# ACC-MB-R0.net
KiCad netlist of a schematic drawn in EAGLE
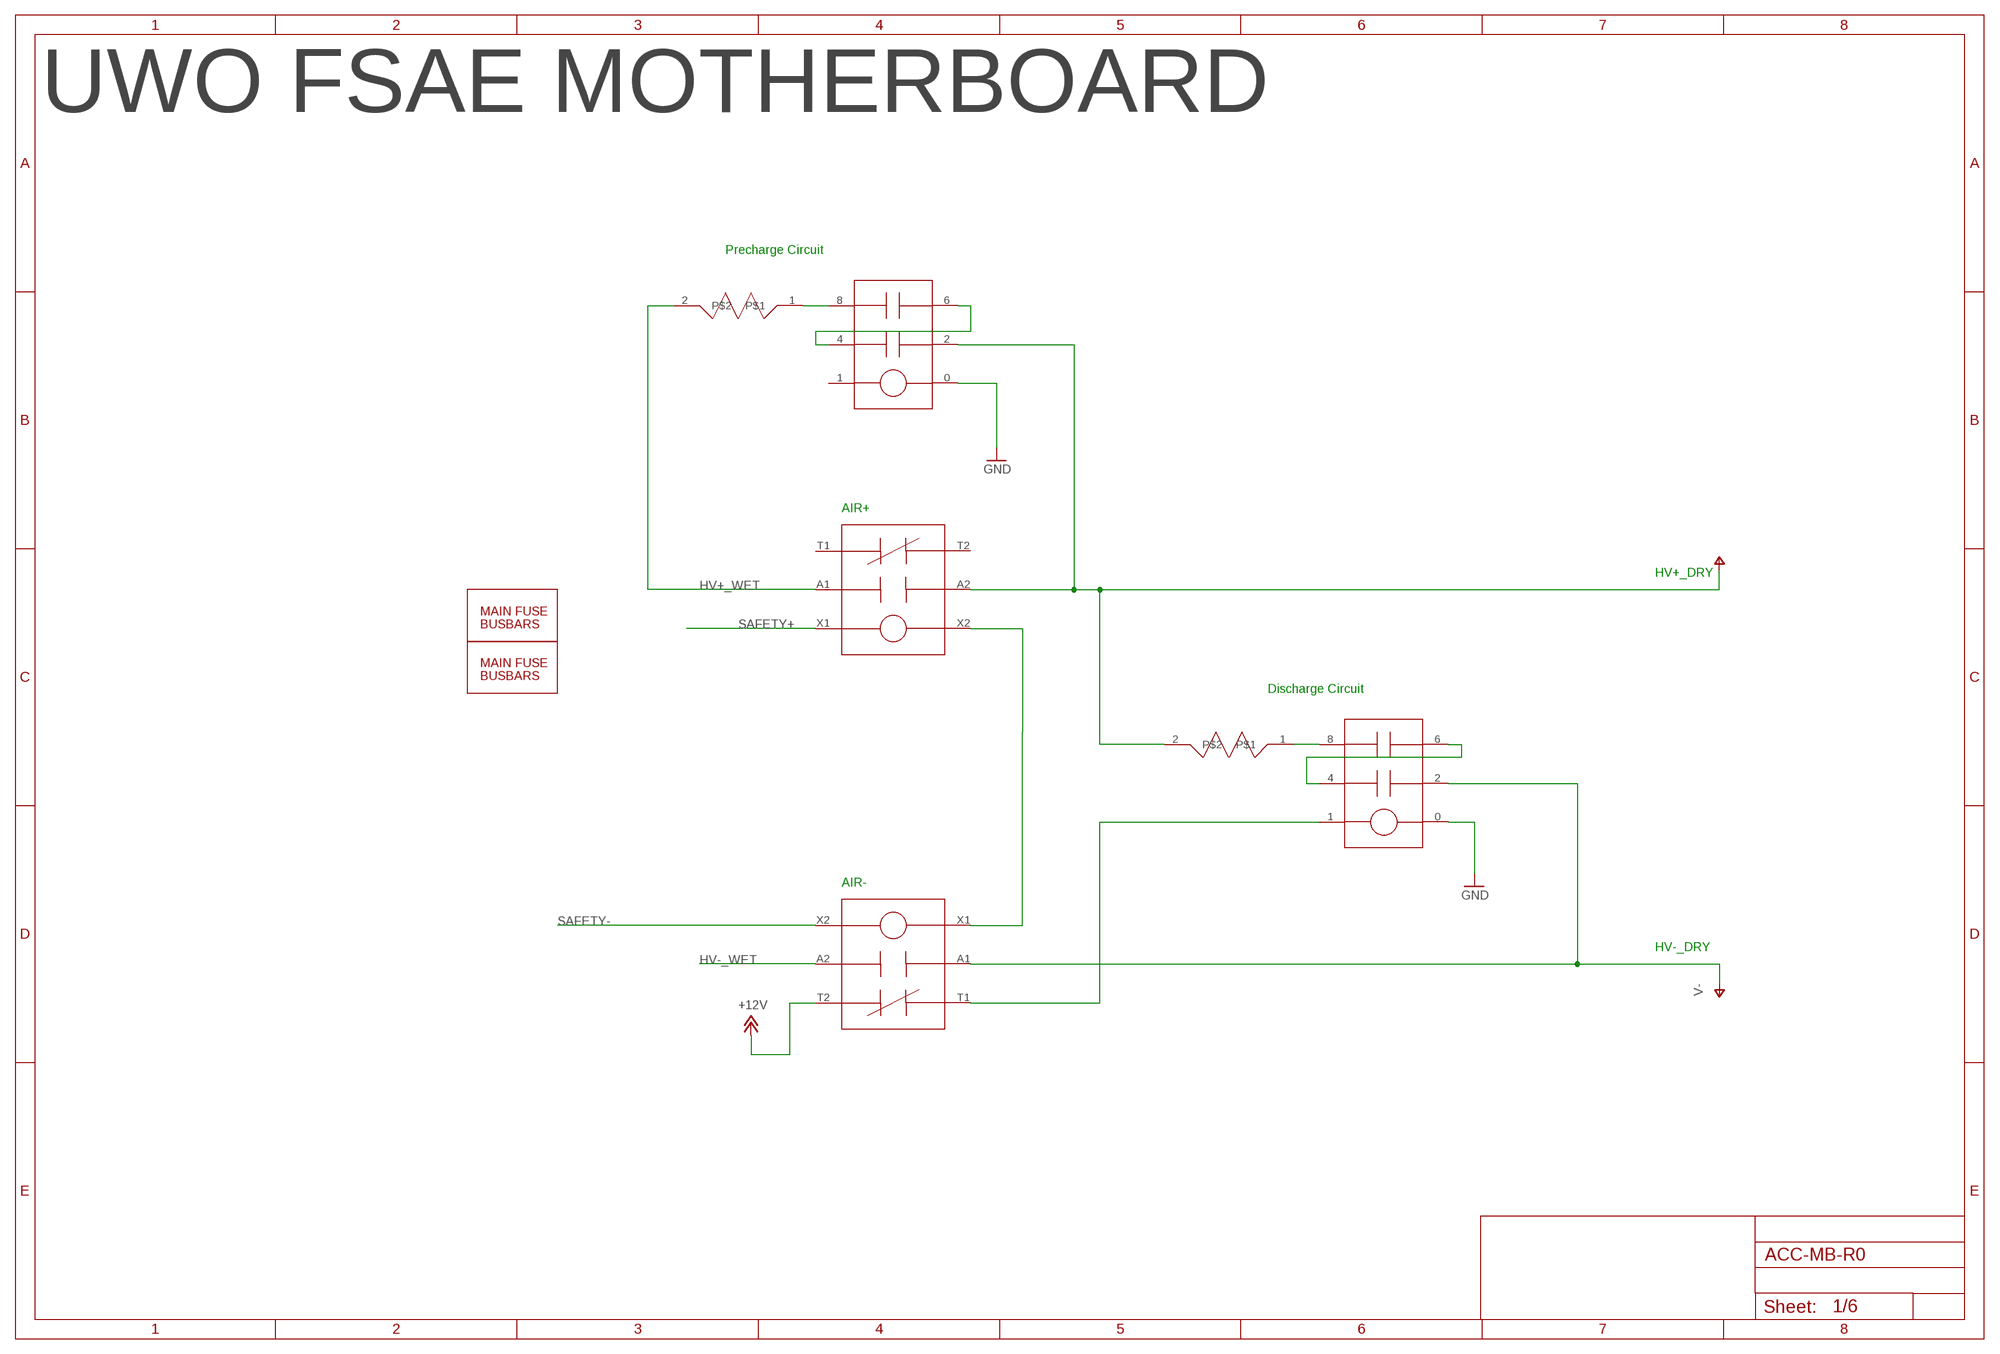
[diagram p0: schematic, sheet 1]
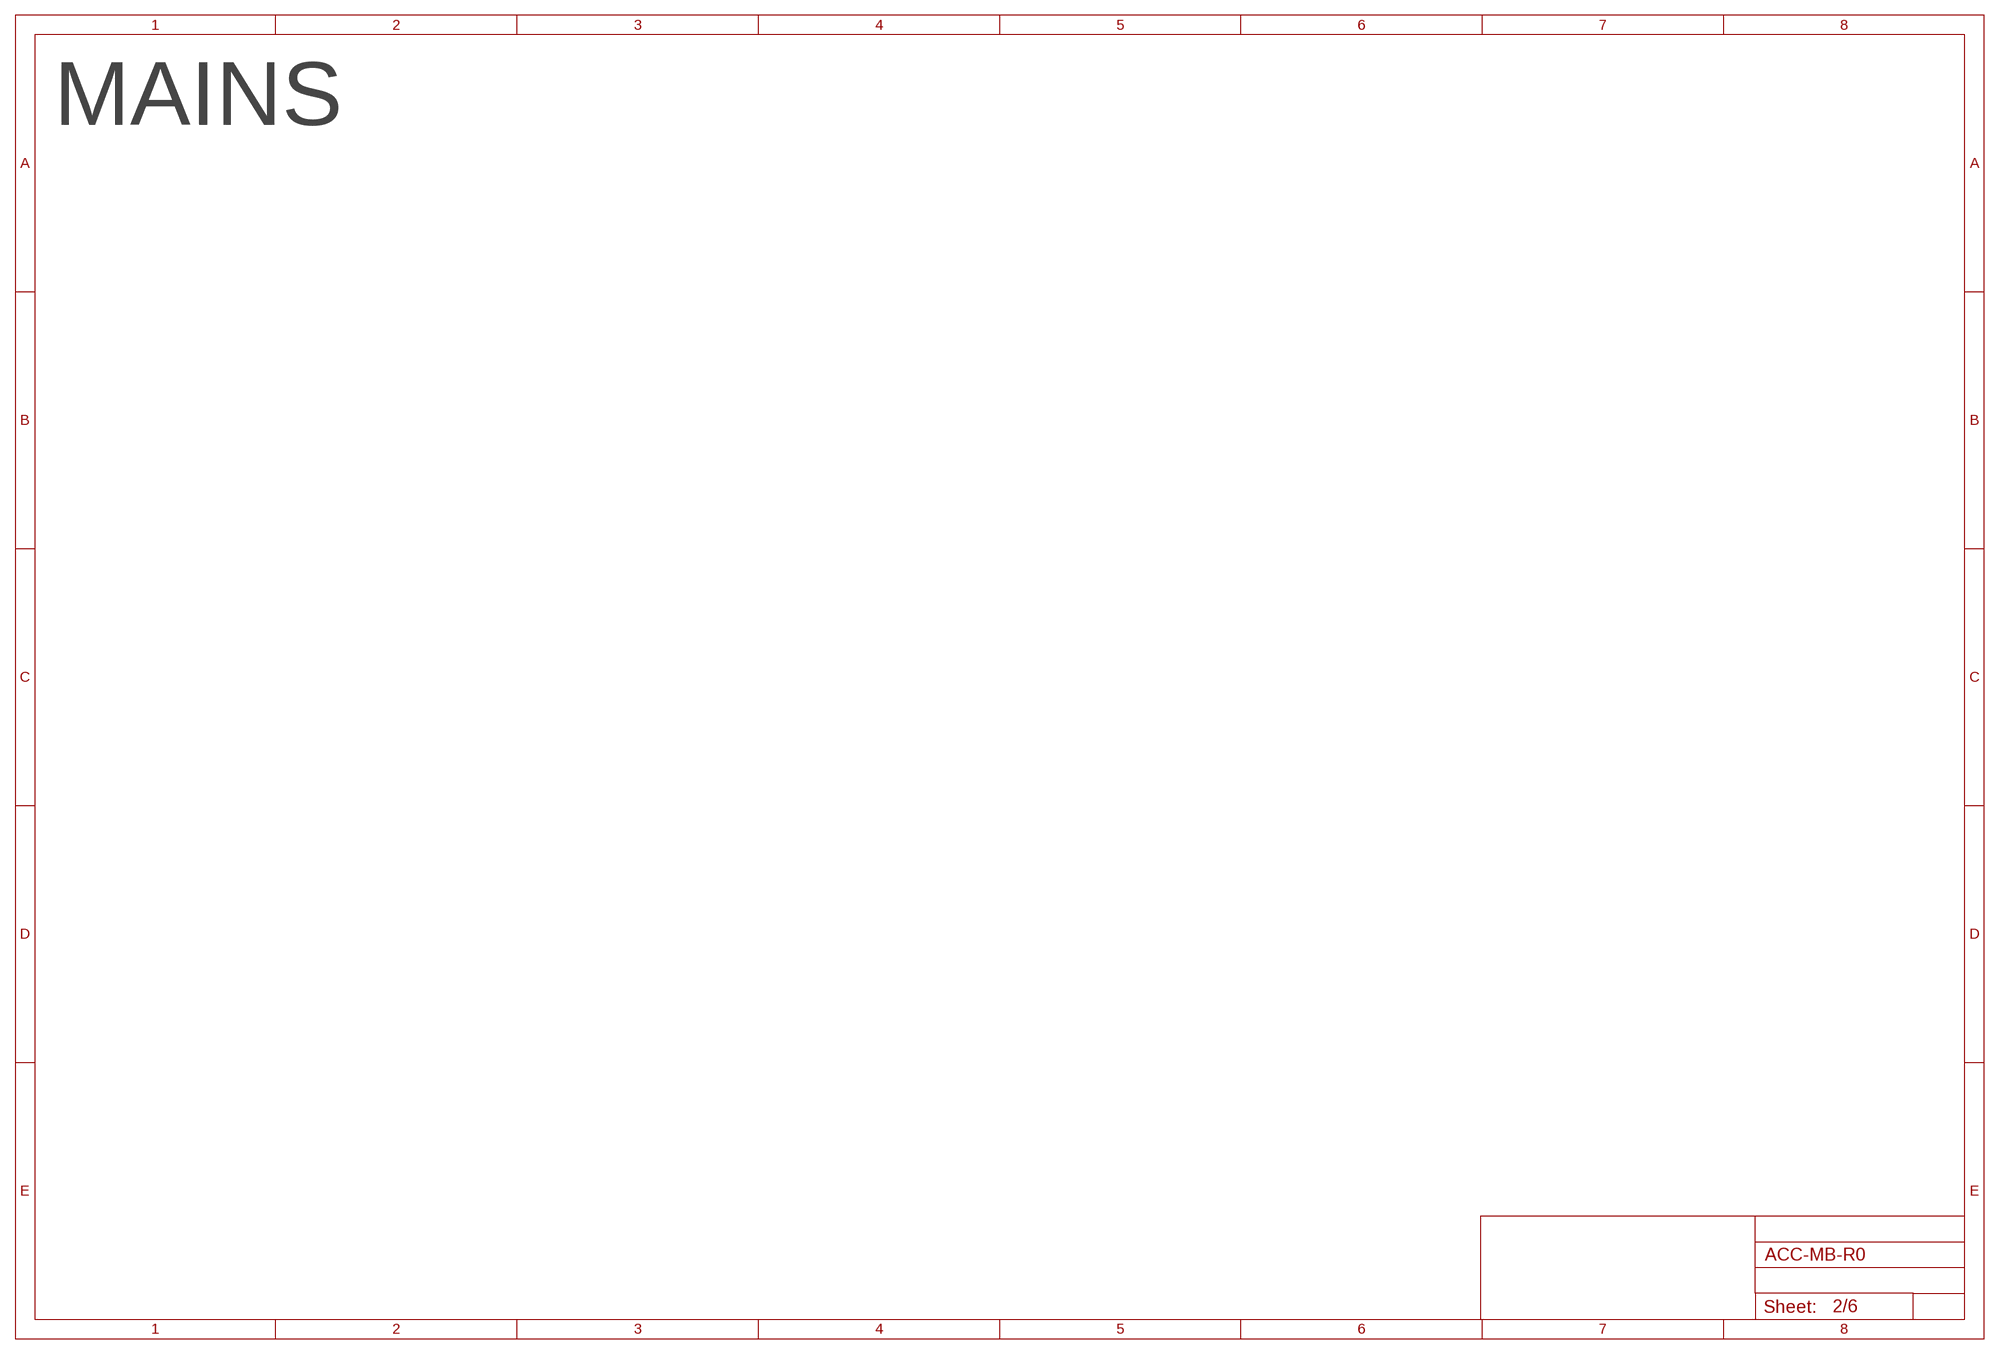
[diagram p1: schematic, sheet 2]
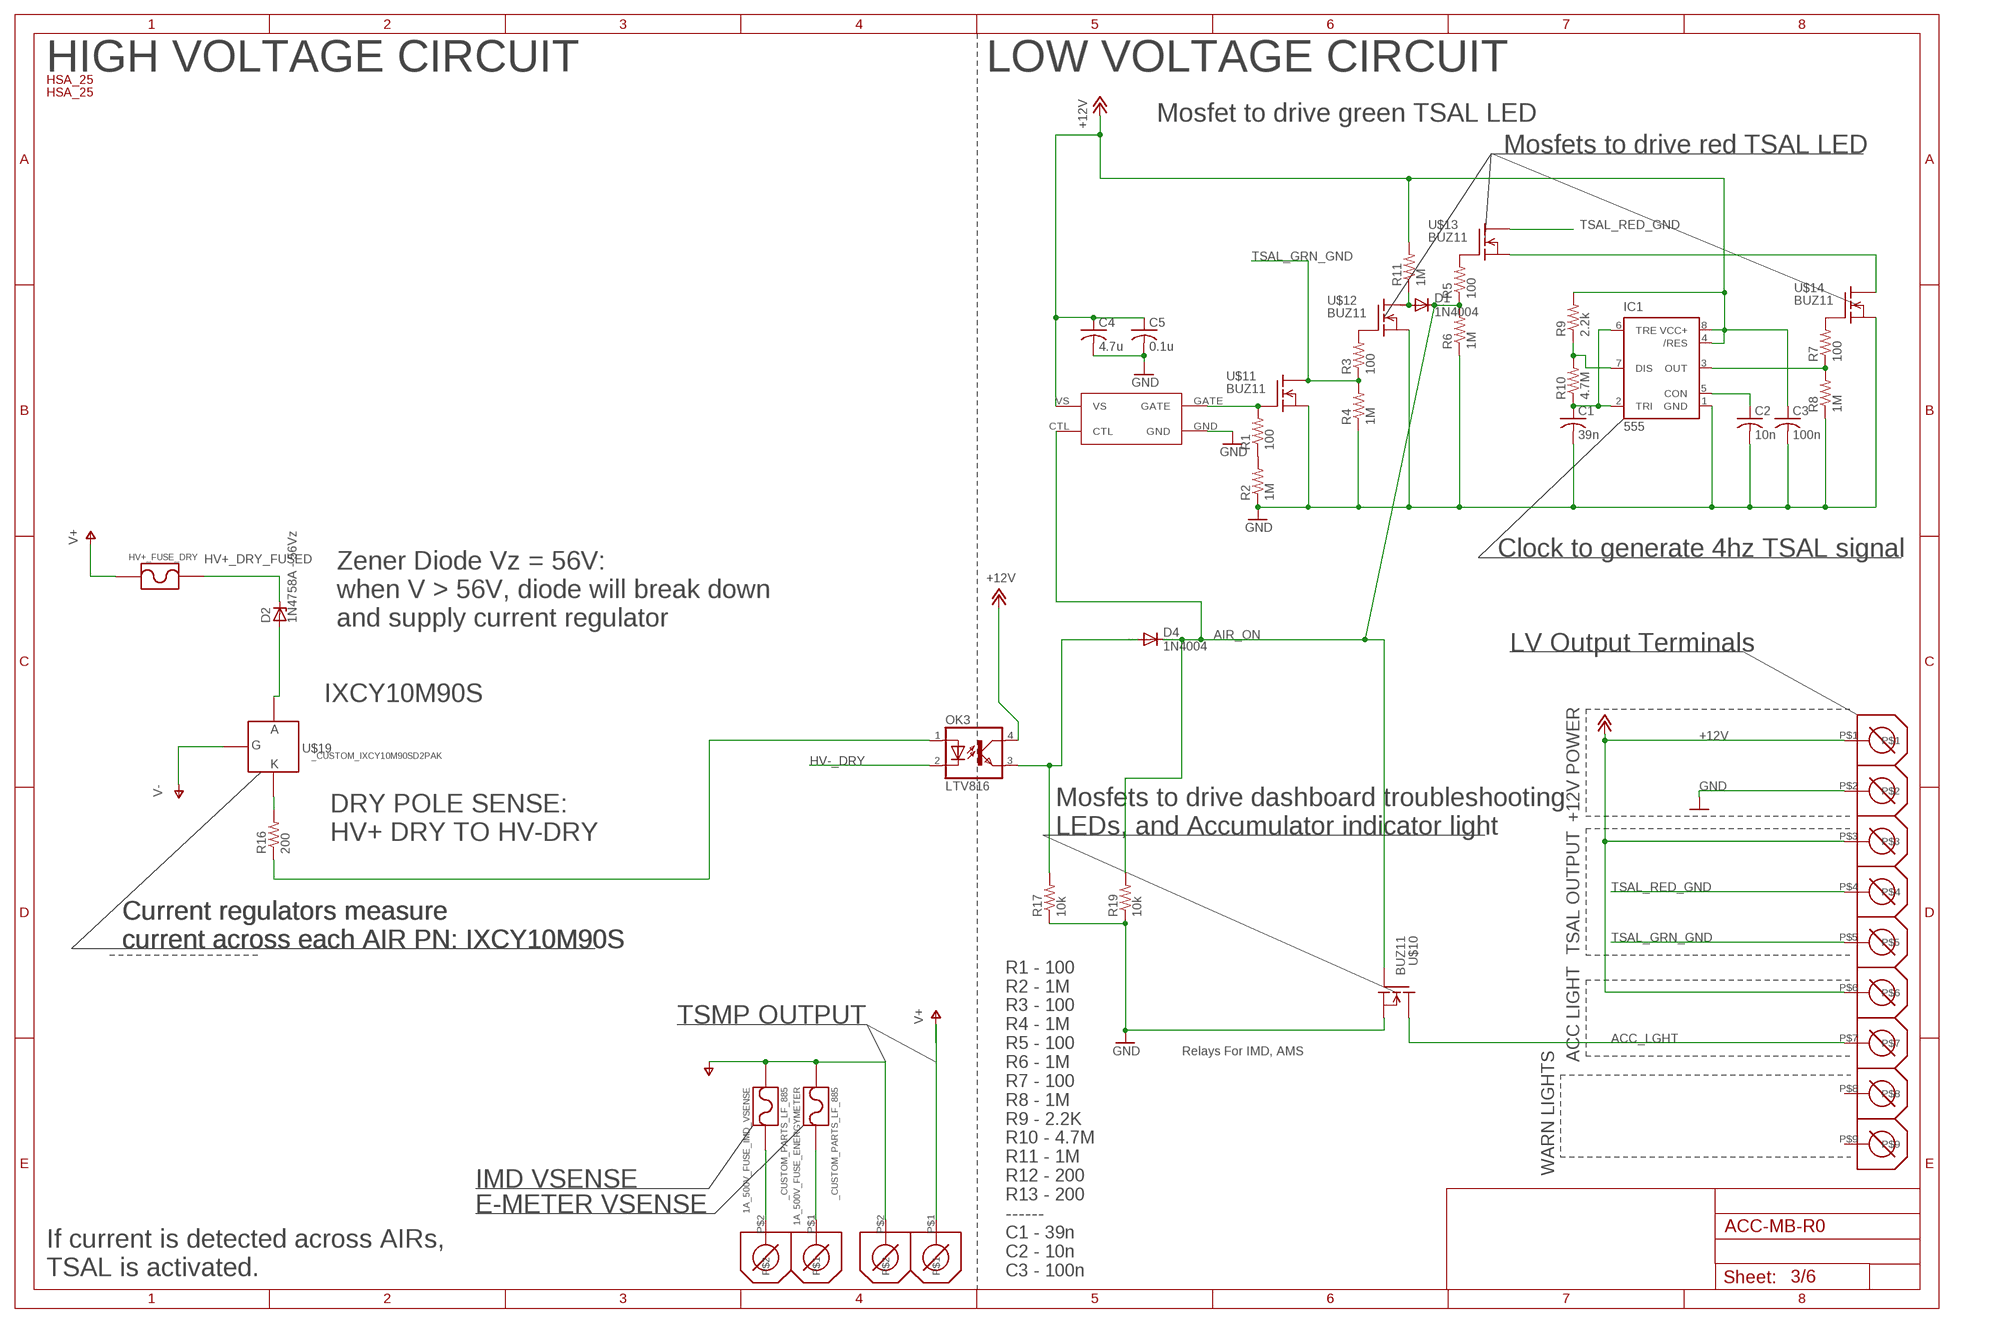
[diagram p2: schematic, sheet 3]
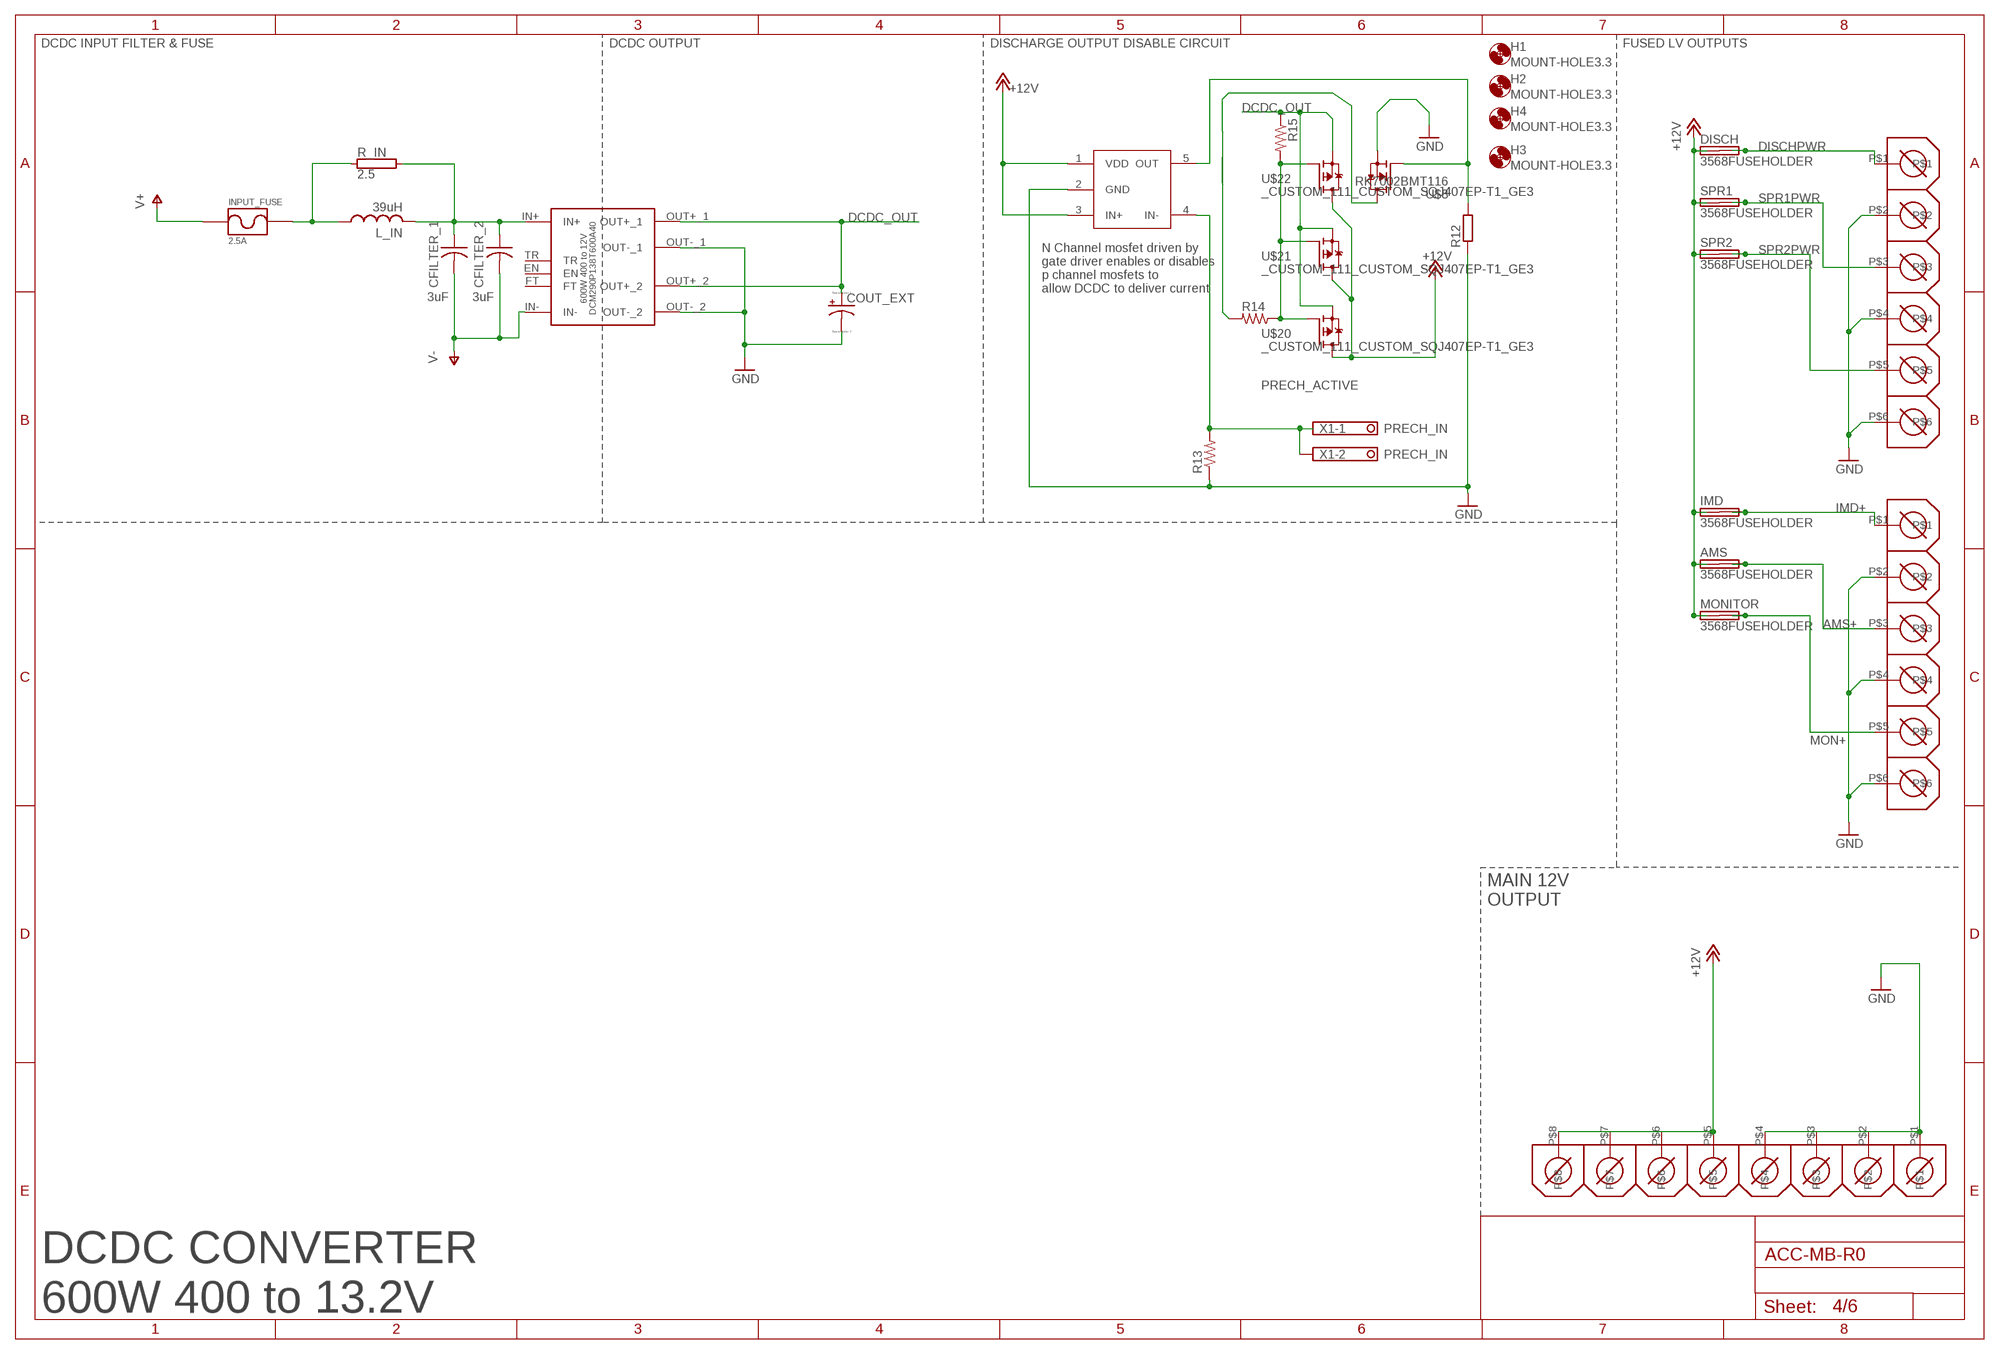
[diagram p3: schematic, sheet 4]
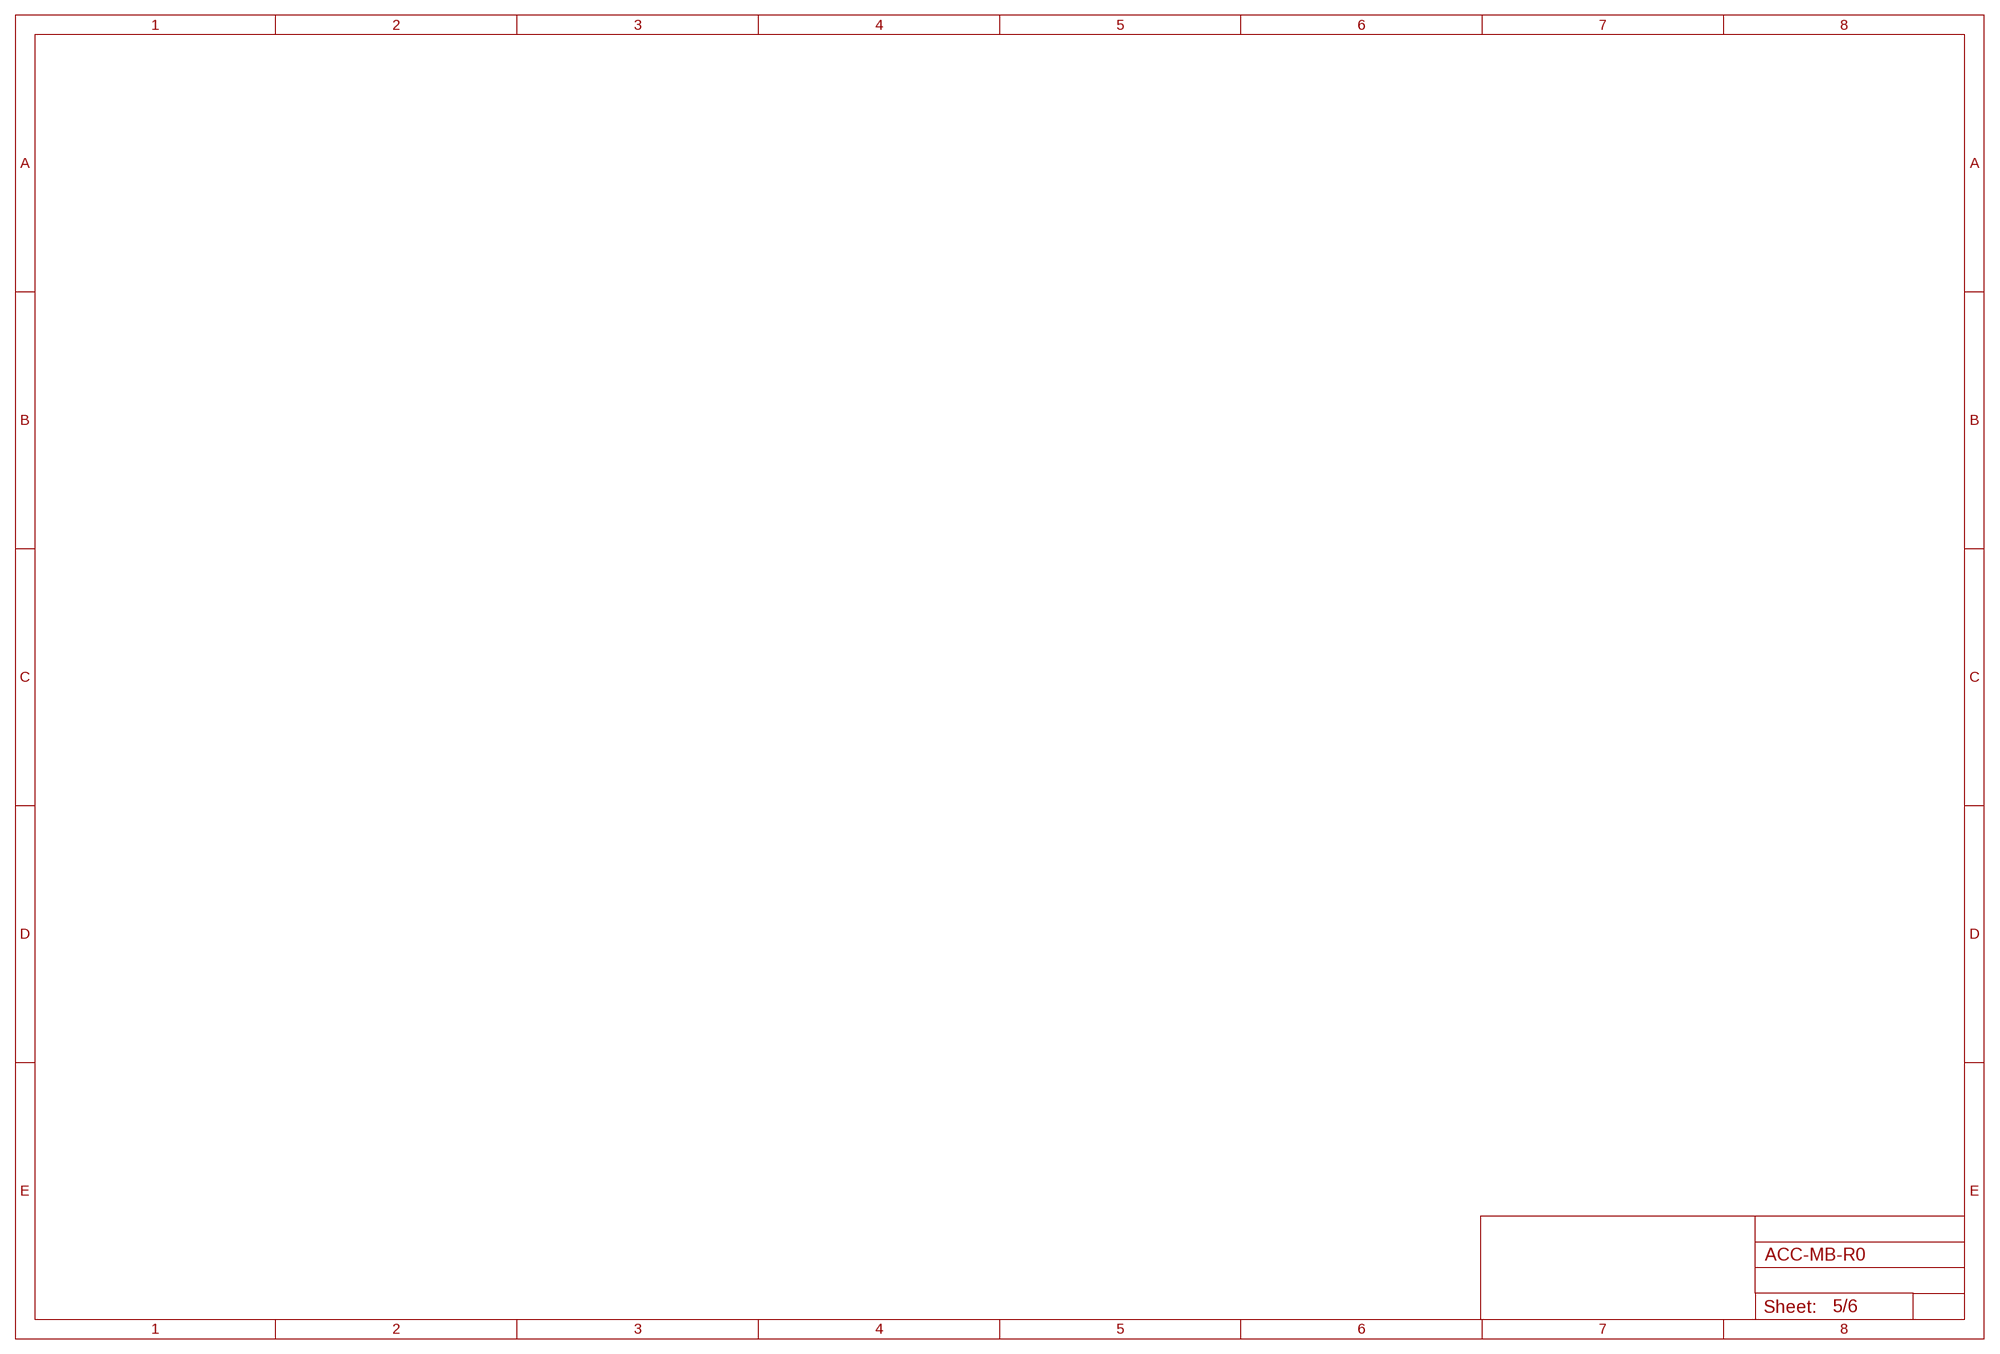
[diagram p4: schematic, sheet 5]
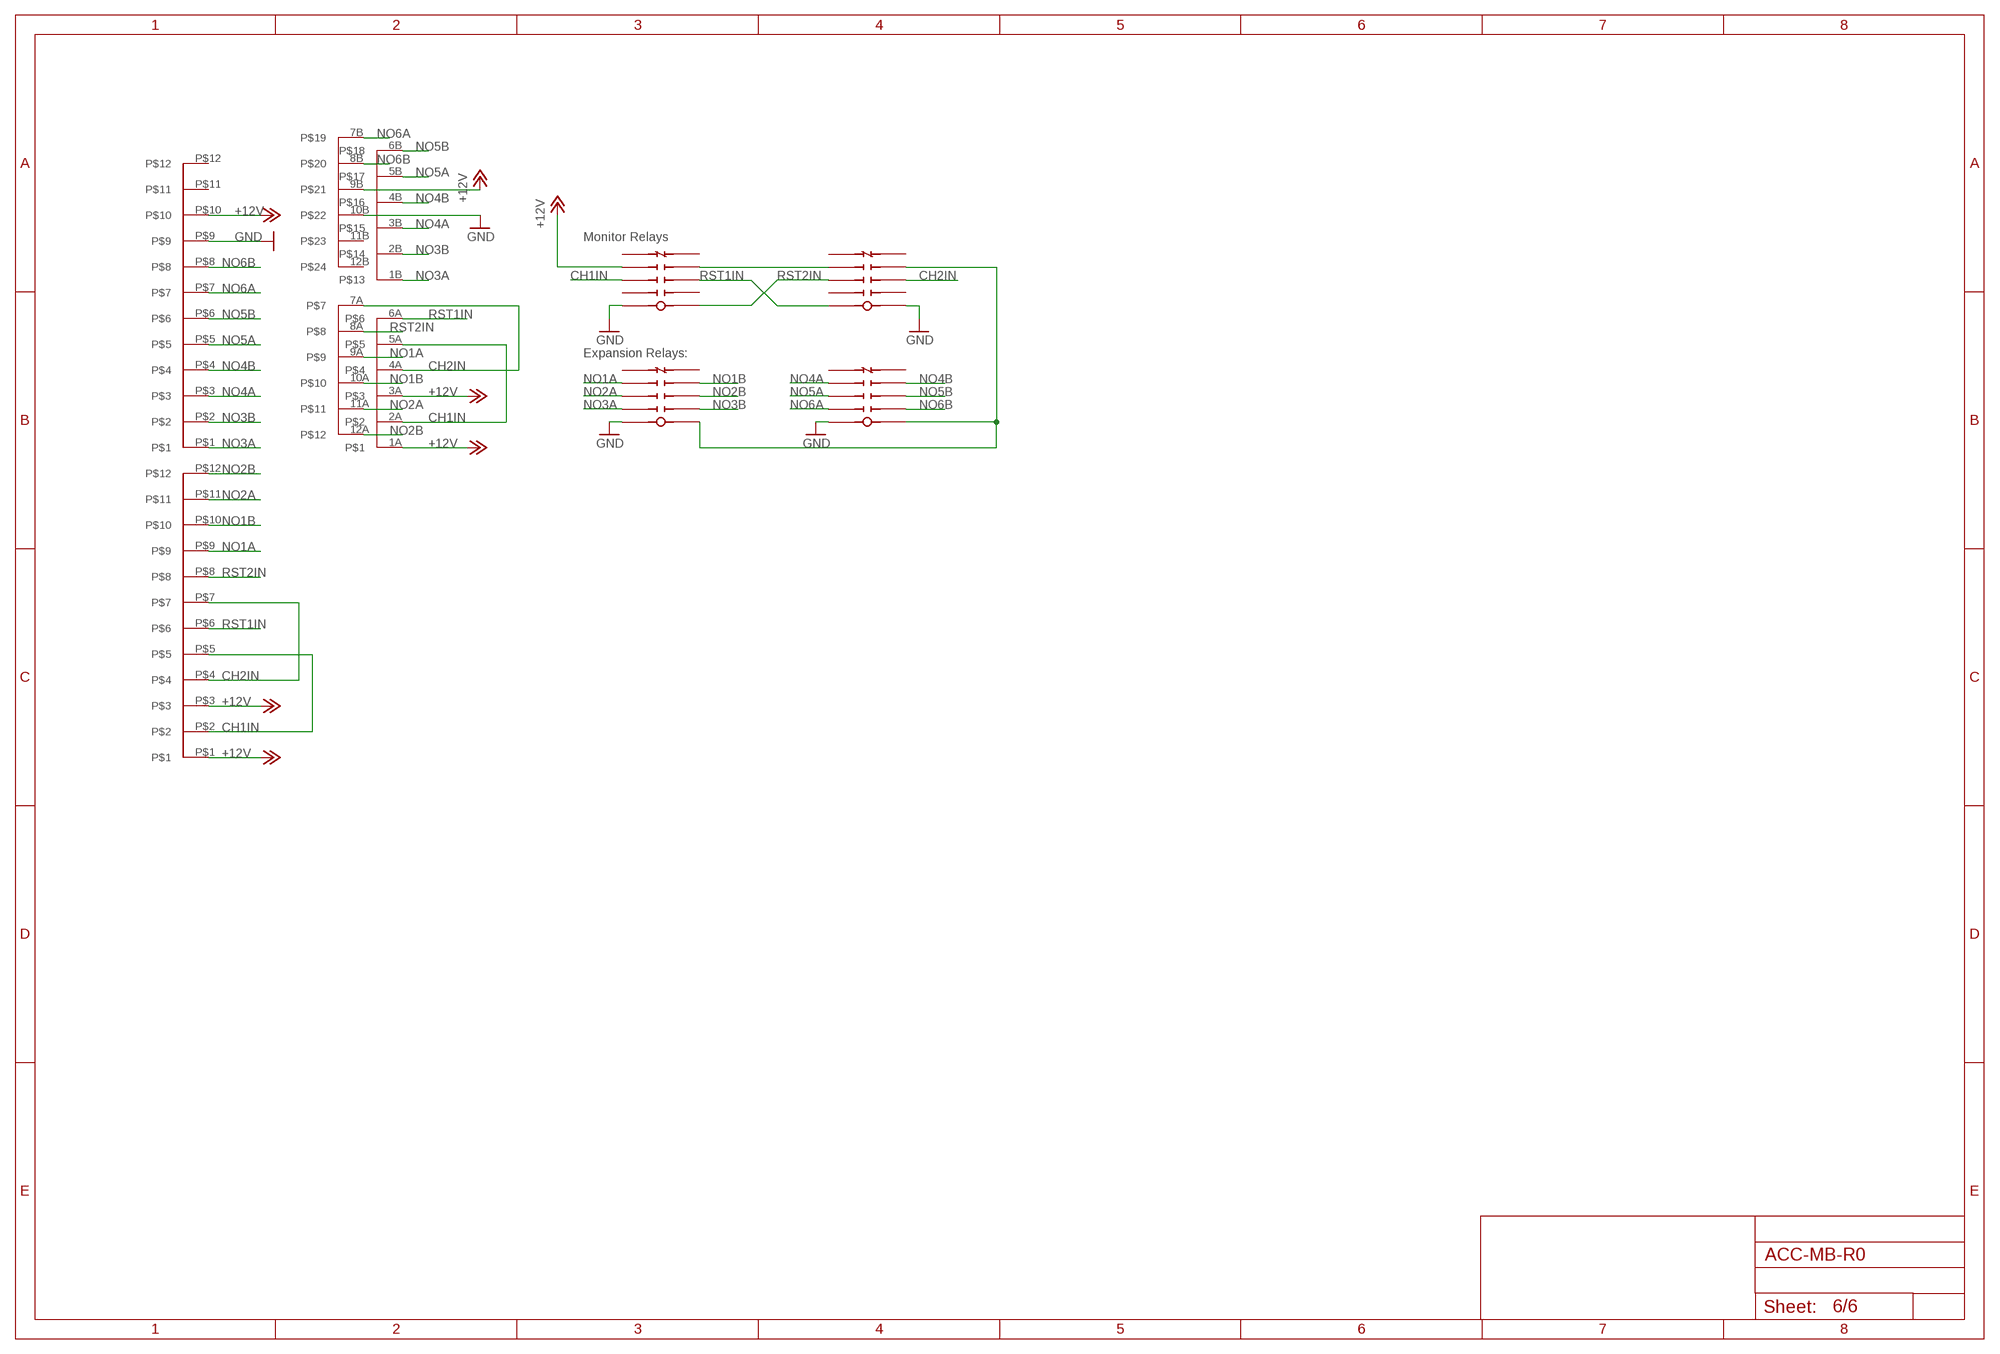
[diagram p5: schematic, sheet 6]

(export (version "E")
  (design (tool "Eeschema 10.0.6"))
  (components
    (comp (ref "1A_500V_FUSE_ENERGYMETER")
      (value "_CUSTOM_PARTS_LF_885")
      (footprint "eagle-import:_CUSTOM_PARTS_LF_885")
      (libsource (lib "eagle-import") (part "_CUSTOM_PARTS_LF_885"))
    )
    (comp (ref "1A_500V_FUSE_IMD_VSENSE")
      (value "_CUSTOM_PARTS_LF_885")
      (footprint "eagle-import:_CUSTOM_PARTS_LF_885")
      (libsource (lib "eagle-import") (part "_CUSTOM_PARTS_LF_885"))
    )
    (comp (ref "C1")
      (value "39n")
      (footprint "eagle-import:C0805")
      (libsource (lib "eagle-import") (part "C-USC0805"))
    )
    (comp (ref "C2")
      (value "10n")
      (footprint "eagle-import:C0805")
      (libsource (lib "eagle-import") (part "C-USC0805"))
    )
    (comp (ref "C3")
      (value "100n")
      (footprint "eagle-import:C0805")
      (libsource (lib "eagle-import") (part "C-USC0805"))
    )
    (comp (ref "C4")
      (value "4.7u")
      (footprint "eagle-import:C0805")
      (libsource (lib "eagle-import") (part "C-USC0805"))
    )
    (comp (ref "C5")
      (value "0.1u")
      (footprint "eagle-import:C0805")
      (libsource (lib "eagle-import") (part "C-USC0805"))
    )
    (comp (ref "D1")
      (value "1N4004")
      (footprint "eagle-import:DO41-10")
      (libsource (lib "eagle-import") (part "1N4004"))
    )
    (comp (ref "D2")
      (value "1N4758A - 56Vz")
      (footprint "eagle-import:ZDIO12.5")
      (libsource (lib "eagle-import") (part "ZENER-DIODEZD-12.5"))
    )
    (comp (ref "D4")
      (value "1N4004")
      (footprint "eagle-import:DO41-10")
      (libsource (lib "eagle-import") (part "1N4004"))
    )
    (comp (ref "HV+_FUSE_DRY")
      (value "_CUSTOM_PARTS_LF_885")
      (footprint "eagle-import:_CUSTOM_PARTS_LF_885")
      (libsource (lib "eagle-import") (part "_CUSTOM_PARTS_LF_885"))
    )
    (comp (ref "IC1")
      (value "555")
      (footprint "eagle-import:DIP08")
      (libsource (lib "eagle-import") (part "555P"))
    )
    (comp (ref "OK3")
      (value "LTV816")
      (footprint "eagle-import:DIL04")
      (libsource (lib "eagle-import") (part "LTV816"))
    )
    (comp (ref "R1")
      (value "100")
      (footprint "eagle-import:R0805_1")
      (libsource (lib "eagle-import") (part "R-US_?{colon}1R0805"))
    )
    (comp (ref "R2")
      (value "1M")
      (footprint "eagle-import:R0805_1")
      (libsource (lib "eagle-import") (part "R-US_?{colon}1R0805"))
    )
    (comp (ref "R3")
      (value "100")
      (footprint "eagle-import:R0805_1")
      (libsource (lib "eagle-import") (part "R-US_?{colon}1R0805"))
    )
    (comp (ref "R4")
      (value "1M")
      (footprint "eagle-import:R0805_1")
      (libsource (lib "eagle-import") (part "R-US_?{colon}1R0805"))
    )
    (comp (ref "R5")
      (value "100")
      (footprint "eagle-import:R0805_1")
      (libsource (lib "eagle-import") (part "R-US_?{colon}1R0805"))
    )
    (comp (ref "R6")
      (value "1M")
      (footprint "eagle-import:R0805_1")
      (libsource (lib "eagle-import") (part "R-US_?{colon}1R0805"))
    )
    (comp (ref "R7")
      (value "100")
      (footprint "eagle-import:R0805_1")
      (libsource (lib "eagle-import") (part "R-US_?{colon}1R0805"))
    )
    (comp (ref "R8")
      (value "1M")
      (footprint "eagle-import:R0805_1")
      (libsource (lib "eagle-import") (part "R-US_?{colon}1R0805"))
    )
    (comp (ref "R9")
      (value "2.2k")
      (footprint "eagle-import:R0805_1")
      (libsource (lib "eagle-import") (part "R-US_?{colon}1R0805"))
    )
    (comp (ref "R10")
      (value "4.7M")
      (footprint "eagle-import:R0805_1")
      (libsource (lib "eagle-import") (part "R-US_?{colon}1R0805"))
    )
    (comp (ref "R11")
      (value "1M")
      (footprint "eagle-import:R0805_1")
      (libsource (lib "eagle-import") (part "R-US_?{colon}1R0805"))
    )
    (comp (ref "R16")
      (value "200")
      (footprint "eagle-import:R2010")
      (libsource (lib "eagle-import") (part "R-US_R2010"))
    )
    (comp (ref "R17")
      (value "10k")
      (footprint "eagle-import:R0805_1")
      (libsource (lib "eagle-import") (part "R-US_?{colon}1R0805"))
    )
    (comp (ref "R19")
      (value "10k")
      (footprint "eagle-import:R0805_1")
      (libsource (lib "eagle-import") (part "R-US_?{colon}1R0805"))
    )
    (comp (ref "U$2")
      (value "HSA25")
      (footprint "eagle-import:HSA_25_FOOT")
      (libsource (lib "eagle-import") (part "HSA25"))
    )
    (comp (ref "U$3")
      (value "HSA25")
      (footprint "eagle-import:HSA_25_FOOT")
      (libsource (lib "eagle-import") (part "HSA25"))
    )
    (comp (ref "U$7")
      (value "PHOENIX_1725724")
      (footprint "eagle-import:1725724_FOOT")
      (libsource (lib "eagle-import") (part "PHOENIX_1725724"))
    )
    (comp (ref "U$10")
      (value "BUZ11")
      (footprint "eagle-import:TO220")
      (libsource (lib "eagle-import") (part "BUZ11"))
    )
    (comp (ref "U$11")
      (value "BUZ11")
      (footprint "eagle-import:TO220")
      (libsource (lib "eagle-import") (part "BUZ11"))
    )
    (comp (ref "U$12")
      (value "BUZ11")
      (footprint "eagle-import:TO220")
      (libsource (lib "eagle-import") (part "BUZ11"))
    )
    (comp (ref "U$13")
      (value "BUZ11")
      (footprint "eagle-import:TO220")
      (libsource (lib "eagle-import") (part "BUZ11"))
    )
    (comp (ref "U$14")
      (value "BUZ11")
      (footprint "eagle-import:TO220")
      (libsource (lib "eagle-import") (part "BUZ11"))
    )
    (comp (ref "U$15")
      (value "MIC4417")
      (footprint "eagle-import:PDM_2019_REVB_MIC4416YM4-TR")
      (libsource (lib "eagle-import") (part "MIC4417"))
    )
    (comp (ref "U$16")
      (value "DCDC_PARTS_282838-2_TE")
      (footprint "eagle-import:DCDC_PARTS_282838-2_FOOT")
      (libsource (lib "eagle-import") (part "DCDC_PARTS_282838-2_TE"))
    )
    (comp (ref "U$17")
      (value "DCDC_PARTS_282838-2_TE")
      (footprint "eagle-import:DCDC_PARTS_282838-2_FOOT")
      (libsource (lib "eagle-import") (part "DCDC_PARTS_282838-2_TE"))
    )
    (comp (ref "U$19")
      (value "_CUSTOM_IXCY10M90SD2PAK")
      (footprint "eagle-import:TO228P991X238-3")
      (libsource (lib "eagle-import") (part "_CUSTOM_IXCY10M90SD2PAK"))
    )
    (comp (ref "U$1")
      (value "G7L")
      (footprint "eagle-import:G7L")
      (libsource (lib "eagle-import") (part "G7L"))
    )
    (comp (ref "U$4")
      (value "TO247RESISTORHEATINK")
      (footprint "eagle-import:_CUSTOM_TO-247-2V")
      (libsource (lib "eagle-import") (part "TO247RESISTORHEATINK"))
    )
    (comp (ref "U$24")
      (value "FUSE_HOLDER")
      (footprint "eagle-import:FUSE_HOLDER")
      (libsource (lib "eagle-import") (part "FUSE_HOLDER"))
    )
    (comp (ref "U$31")
      (value "GV224")
      (footprint "eagle-import:GV224")
      (libsource (lib "eagle-import") (part "GV224"))
    )
    (comp (ref "U$32")
      (value "GV224")
      (footprint "eagle-import:GV224")
      (libsource (lib "eagle-import") (part "GV224"))
    )
    (comp (ref "U$33")
      (value "FUSE_HOLDER")
      (footprint "eagle-import:FUSE_HOLDER")
      (libsource (lib "eagle-import") (part "FUSE_HOLDER"))
    )
    (comp (ref "U$34")
      (value "G7L")
      (footprint "eagle-import:G7L")
      (libsource (lib "eagle-import") (part "G7L"))
    )
    (comp (ref "U$35")
      (value "TO247RESISTORHEATINK")
      (footprint "eagle-import:_CUSTOM_TO-247-2V")
      (libsource (lib "eagle-import") (part "TO247RESISTORHEATINK"))
    )
    (comp (ref "U$23")
      (value "1777642_PHOENIX")
      (footprint "eagle-import:1777642_FOOTPRINT")
      (libsource (lib "eagle-import") (part "1777642_PHOENIX"))
    )
    (comp (ref "U$25")
      (value "1777642_PHOENIX")
      (footprint "eagle-import:1777642_FOOTPRINT")
      (libsource (lib "eagle-import") (part "1777642_PHOENIX"))
    )
    (comp (ref "U$26")
      (value "DTM1312PA12BR008")
      (footprint "eagle-import:DE_12X2_PIN_HEADER")
      (libsource (lib "eagle-import") (part "DTM1312PA12BR008"))
    )
    (comp (ref "U$27")
      (value "SR4M4012_TE")
      (footprint "eagle-import:SR4M4012_FOOT")
      (libsource (lib "eagle-import") (part "SR4M4012_TE"))
    )
    (comp (ref "U$28")
      (value "SR4M4012_TE")
      (footprint "eagle-import:SR4M4012_FOOT")
      (libsource (lib "eagle-import") (part "SR4M4012_TE"))
    )
    (comp (ref "U$29")
      (value "SR4M4012_TE")
      (footprint "eagle-import:SR4M4012_FOOT")
      (libsource (lib "eagle-import") (part "SR4M4012_TE"))
    )
    (comp (ref "U$30")
      (value "SR4M4012_TE")
      (footprint "eagle-import:SR4M4012_FOOT")
      (libsource (lib "eagle-import") (part "SR4M4012_TE"))
    )
    (comp (ref "AMS")
      (value "3568FUSEHOLDER")
      (footprint "eagle-import:3568")
      (libsource (lib "eagle-import") (part "3568FUSEHOLDER"))
    )
    (comp (ref "CFILTER_1")
      (value "3uF")
      (footprint "eagle-import:CERALINK_FA3")
      (libsource (lib "eagle-import") (part "B58035U5305M062"))
    )
    (comp (ref "CFILTER_2")
      (value "3uF")
      (footprint "eagle-import:CERALINK_FA3")
      (libsource (lib "eagle-import") (part "B58035U5305M062"))
    )
    (comp (ref "COUT_EXT")
      (value "CPOL-USE7.5-16")
      (footprint "eagle-import:E7,5-16")
      (libsource (lib "eagle-import") (part "CPOL-USE7.5-16"))
    )
    (comp (ref "DCM290P138T600A40")
      (value "600W 400 to 12V")
      (footprint "eagle-import:VICOR_CHIP_HEATSINK")
      (libsource (lib "eagle-import") (part "VICOR_CHIP_WITH_HEATSINK"))
    )
    (comp (ref "DISCH")
      (value "3568FUSEHOLDER")
      (footprint "eagle-import:3568")
      (libsource (lib "eagle-import") (part "3568FUSEHOLDER"))
    )
    (comp (ref "H1")
      (value "MOUNT-HOLE3.3")
      (footprint "eagle-import:3,3")
      (libsource (lib "eagle-import") (part "MOUNT-HOLE3.3"))
    )
    (comp (ref "H2")
      (value "MOUNT-HOLE3.3")
      (footprint "eagle-import:3,3")
      (libsource (lib "eagle-import") (part "MOUNT-HOLE3.3"))
    )
    (comp (ref "H3")
      (value "MOUNT-HOLE3.3")
      (footprint "eagle-import:3,3")
      (libsource (lib "eagle-import") (part "MOUNT-HOLE3.3"))
    )
    (comp (ref "H4")
      (value "MOUNT-HOLE3.3")
      (footprint "eagle-import:3,3")
      (libsource (lib "eagle-import") (part "MOUNT-HOLE3.3"))
    )
    (comp (ref "IMD")
      (value "3568FUSEHOLDER")
      (footprint "eagle-import:3568")
      (libsource (lib "eagle-import") (part "3568FUSEHOLDER"))
    )
    (comp (ref "INPUT_FUSE")
      (value "2.5A")
      (footprint "eagle-import:_CUSTOM_PARTS_LF_885")
      (libsource (lib "eagle-import") (part "_CUSTOM_PARTS_LF_885"))
    )
    (comp (ref "L_IN")
      (value "39uH")
      (footprint "eagle-import:L_1510_NONSTANDARD")
      (libsource (lib "eagle-import") (part "SRP1770TA-390M"))
    )
    (comp (ref "MONITOR")
      (value "3568FUSEHOLDER")
      (footprint "eagle-import:3568")
      (libsource (lib "eagle-import") (part "3568FUSEHOLDER"))
    )
    (comp (ref "R12")
      (value "R-EU_R0805")
      (footprint "eagle-import:R0805")
      (libsource (lib "eagle-import") (part "R-EU_R0805"))
    )
    (comp (ref "R13")
      (value "R-US_R0805")
      (footprint "eagle-import:R0805")
      (libsource (lib "eagle-import") (part "R-US_R0805"))
    )
    (comp (ref "R14")
      (value "R-US_R0805")
      (footprint "eagle-import:R0805")
      (libsource (lib "eagle-import") (part "R-US_R0805"))
    )
    (comp (ref "R15")
      (value "R-US_R0805")
      (footprint "eagle-import:R0805")
      (libsource (lib "eagle-import") (part "R-US_R0805"))
    )
    (comp (ref "R_IN")
      (value "2.5")
      (footprint "eagle-import:TO-247-2V")
      (libsource (lib "eagle-import") (part "RMG100-V"))
    )
    (comp (ref "SPR1")
      (value "3568FUSEHOLDER")
      (footprint "eagle-import:3568")
      (libsource (lib "eagle-import") (part "3568FUSEHOLDER"))
    )
    (comp (ref "SPR2")
      (value "3568FUSEHOLDER")
      (footprint "eagle-import:3568")
      (libsource (lib "eagle-import") (part "3568FUSEHOLDER"))
    )
    (comp (ref "U$5")
      (value "1935200_PHOENIX")
      (footprint "eagle-import:1777587_FOOT")
      (libsource (lib "eagle-import") (part "1935200_PHOENIX"))
    )
    (comp (ref "U$6")
      (value "1935200_PHOENIX")
      (footprint "eagle-import:1777587_FOOT")
      (libsource (lib "eagle-import") (part "1935200_PHOENIX"))
    )
    (comp (ref "U$8")
      (value "RK7002BMT116")
      (footprint "eagle-import:SOT23")
      (libsource (lib "eagle-import") (part "RK7002BMT116"))
    )
    (comp (ref "U$9")
      (value "1777600_PHOENIX")
      (footprint "eagle-import:1777600_FOOT")
      (libsource (lib "eagle-import") (part "1777600_PHOENIX"))
    )
    (comp (ref "U$18")
      (value "UCC27511AQDBVRQ1")
      (footprint "eagle-import:SOT23-5L")
      (libsource (lib "eagle-import") (part "UCC27511AQDBVRQ1"))
    )
    (comp (ref "U$20")
      (value "_CUSTOM_111_CUSTOM_SQJ407EP-T1_GE3")
      (footprint "eagle-import:_CUSTOM_111_CUSTOM_TRANS_SIRA90DP-T1-GE3")
      (libsource (lib "eagle-import") (part "_CUSTOM_111_CUSTOM_SQJ407EP-T1_GE3"))
    )
    (comp (ref "U$21")
      (value "_CUSTOM_111_CUSTOM_SQJ407EP-T1_GE3")
      (footprint "eagle-import:_CUSTOM_111_CUSTOM_TRANS_SIRA90DP-T1-GE3")
      (libsource (lib "eagle-import") (part "_CUSTOM_111_CUSTOM_SQJ407EP-T1_GE3"))
    )
    (comp (ref "U$22")
      (value "_CUSTOM_111_CUSTOM_SQJ407EP-T1_GE3")
      (footprint "eagle-import:_CUSTOM_111_CUSTOM_TRANS_SIRA90DP-T1-GE3")
      (libsource (lib "eagle-import") (part "_CUSTOM_111_CUSTOM_SQJ407EP-T1_GE3"))
    )
    (comp (ref "X1")
      (value "PRECH_IN")
      (footprint "eagle-import:1751248")
      (libsource (lib "eagle-import") (part "1751248"))
    )
  )
  (nets
    (net (code "1") (name "+12V") (class "Default")
      (node (ref "AMS") (pin "L1") (pinfunction "1A_L1") (pintype "passive"))
      (node (ref "AMS") (pin "L2") (pinfunction "1B_L2") (pintype "passive"))
      (node (ref "C3") (pin "1") (pinfunction "1_1") (pintype "passive"))
      (node (ref "C4") (pin "1") (pinfunction "1_1") (pintype "passive"))
      (node (ref "C5") (pin "1") (pinfunction "1_1") (pintype "passive"))
      (node (ref "DISCH") (pin "L1") (pinfunction "1A_L1") (pintype "passive"))
      (node (ref "DISCH") (pin "L2") (pinfunction "1B_L2") (pintype "passive"))
      (node (ref "IC1") (pin "4") (pinfunction "/RES_4") (pintype "input"))
      (node (ref "IC1") (pin "8") (pinfunction "VCC+_8") (pintype "power_in"))
      (node (ref "IMD") (pin "L1") (pinfunction "1A_L1") (pintype "passive"))
      (node (ref "IMD") (pin "L2") (pinfunction "1B_L2") (pintype "passive"))
      (node (ref "MONITOR") (pin "L1") (pinfunction "1A_L1") (pintype "passive"))
      (node (ref "MONITOR") (pin "L2") (pinfunction "1B_L2") (pintype "passive"))
      (node (ref "OK3") (pin "4") (pinfunction "COL_4") (pintype "passive"))
      (node (ref "R11") (pin "2") (pinfunction "2_2") (pintype "passive"))
      (node (ref "R9") (pin "2") (pinfunction "2_2") (pintype "passive"))
      (node (ref "SPR1") (pin "L1") (pinfunction "1A_L1") (pintype "passive"))
      (node (ref "SPR1") (pin "L2") (pinfunction "1B_L2") (pintype "passive"))
      (node (ref "SPR2") (pin "L1") (pinfunction "1A_L1") (pintype "passive"))
      (node (ref "SPR2") (pin "L2") (pinfunction "1B_L2") (pintype "passive"))
      (node (ref "U$15") (pin "VS") (pinfunction "VS_VS") (pintype "bidirectional"))
      (node (ref "U$18") (pin "1") (pinfunction "VDD_1") (pintype "bidirectional"))
      (node (ref "U$18") (pin "3") (pinfunction "IN+_3") (pintype "bidirectional"))
      (node (ref "U$20") (pin "5") (pinfunction "D_5") (pintype "passive"))
      (node (ref "U$21") (pin "5") (pinfunction "D_5") (pintype "passive"))
      (node (ref "U$22") (pin "5") (pinfunction "D_5") (pintype "passive"))
      (node (ref "U$23") (pin "P$10") (pinfunction "P$10_P$10") (pintype "bidirectional"))
      (node (ref "U$25") (pin "P$1") (pinfunction "P$1_P$1") (pintype "bidirectional"))
      (node (ref "U$25") (pin "P$3") (pinfunction "P$3_P$3") (pintype "bidirectional"))
      (node (ref "U$26") (pin "1A") (pinfunction "P$1_1A") (pintype "bidirectional"))
      (node (ref "U$26") (pin "3A") (pinfunction "P$3_3A") (pintype "bidirectional"))
      (node (ref "U$26") (pin "9B") (pinfunction "P$21_9B") (pintype "bidirectional"))
      (node (ref "U$27") (pin "NOA3") (pinfunction "NOA3_NOA3") (pintype "bidirectional"))
      (node (ref "U$32") (pin "T2") (pinfunction "T2_T2") (pintype "bidirectional"))
      (node (ref "U$7") (pin "P$1") (pinfunction "P$1_P$1") (pintype "bidirectional"))
      (node (ref "U$7") (pin "P$3") (pinfunction "P$3_P$3") (pintype "bidirectional"))
      (node (ref "U$7") (pin "P$6") (pinfunction "P$6_P$6") (pintype "bidirectional"))
      (node (ref "U$9") (pin "P$5") (pinfunction "P$5_P$5") (pintype "bidirectional"))
      (node (ref "U$9") (pin "P$6") (pinfunction "P$6_P$6") (pintype "bidirectional"))
      (node (ref "U$9") (pin "P$7") (pinfunction "P$7_P$7") (pintype "bidirectional"))
      (node (ref "U$9") (pin "P$8") (pinfunction "P$8_P$8") (pintype "bidirectional"))
    )
    (net (code "2") (name "ACC_LGHT") (class "Default")
      (node (ref "U$10") (pin "2") (pinfunction "D_2") (pintype "passive"))
      (node (ref "U$7") (pin "P$7") (pinfunction "P$7_P$7") (pintype "bidirectional"))
    )
    (net (code "3") (name "AIR_ON") (class "Default")
      (node (ref "D1") (pin "C") (pinfunction "C_C") (pintype "passive"))
      (node (ref "D4") (pin "C") (pinfunction "C_C") (pintype "passive"))
      (node (ref "R19") (pin "2") (pinfunction "2_2") (pintype "passive"))
      (node (ref "R5") (pin "1") (pinfunction "1_1") (pintype "passive"))
      (node (ref "R6") (pin "2") (pinfunction "2_2") (pintype "passive"))
      (node (ref "U$10") (pin "1") (pinfunction "G_1") (pintype "passive"))
      (node (ref "U$15") (pin "CTL") (pinfunction "CTL_CTL") (pintype "bidirectional"))
    )
    (net (code "4") (name "AMS+") (class "Default")
      (node (ref "AMS") (pin "R1") (pinfunction "2A_R1") (pintype "passive"))
      (node (ref "AMS") (pin "R2") (pinfunction "2B_R2") (pintype "passive"))
      (node (ref "U$5") (pin "P$3") (pinfunction "P$3_P$3") (pintype "bidirectional"))
    )
    (net (code "5") (name "CH1IN") (class "Default")
      (node (ref "U$25") (pin "P$2") (pinfunction "P$2_P$2") (pintype "bidirectional"))
      (node (ref "U$25") (pin "P$5") (pinfunction "P$5_P$5") (pintype "bidirectional"))
      (node (ref "U$26") (pin "2A") (pinfunction "P$2_2A") (pintype "bidirectional"))
      (node (ref "U$26") (pin "5A") (pinfunction "P$5_5A") (pintype "bidirectional"))
      (node (ref "U$27") (pin "NOA2") (pinfunction "NOA2_NOA2") (pintype "bidirectional"))
    )
    (net (code "6") (name "CH2IN") (class "Default")
      (node (ref "U$25") (pin "P$4") (pinfunction "P$4_P$4") (pintype "bidirectional"))
      (node (ref "U$25") (pin "P$7") (pinfunction "P$7_P$7") (pintype "bidirectional"))
      (node (ref "U$26") (pin "4A") (pinfunction "P$4_4A") (pintype "bidirectional"))
      (node (ref "U$26") (pin "7A") (pinfunction "P$7_7A") (pintype "bidirectional"))
      (node (ref "U$28") (pin "NOB2") (pinfunction "NOB2_NOB2") (pintype "bidirectional"))
    )
    (net (code "7") (name "DCDC_OUT") (class "Default")
      (node (ref "COUT_EXT") (pin "+") (pinfunction "+_+") (pintype "passive"))
      (node (ref "DCM290P138T600A40") (pin "OUT+_1") (pinfunction "OUT+_1_OUT+_1") (pintype "bidirectional"))
      (node (ref "DCM290P138T600A40") (pin "OUT+_2") (pinfunction "OUT+_2_OUT+_2") (pintype "bidirectional"))
      (node (ref "R15") (pin "1") (pinfunction "1_1") (pintype "passive"))
      (node (ref "U$20") (pin "1") (pinfunction "S_1") (pintype "passive"))
      (node (ref "U$20") (pin "2") (pinfunction "S_2") (pintype "passive"))
      (node (ref "U$20") (pin "3") (pinfunction "S_3") (pintype "passive"))
      (node (ref "U$21") (pin "1") (pinfunction "S_1") (pintype "passive"))
      (node (ref "U$21") (pin "2") (pinfunction "S_2") (pintype "passive"))
      (node (ref "U$21") (pin "3") (pinfunction "S_3") (pintype "passive"))
      (node (ref "U$22") (pin "1") (pinfunction "S_1") (pintype "passive"))
      (node (ref "U$22") (pin "2") (pinfunction "S_2") (pintype "passive"))
      (node (ref "U$22") (pin "3") (pinfunction "S_3") (pintype "passive"))
    )
    (net (code "8") (name "DISCHPWR") (class "Default")
      (node (ref "DISCH") (pin "R1") (pinfunction "2A_R1") (pintype "passive"))
      (node (ref "DISCH") (pin "R2") (pinfunction "2B_R2") (pintype "passive"))
      (node (ref "U$6") (pin "P$1") (pinfunction "P$1_P$1") (pintype "bidirectional"))
    )
    (net (code "9") (name "GND") (class "Default")
      (node (ref "C1") (pin "2") (pinfunction "2_2") (pintype "passive"))
      (node (ref "C2") (pin "2") (pinfunction "2_2") (pintype "passive"))
      (node (ref "C3") (pin "2") (pinfunction "2_2") (pintype "passive"))
      (node (ref "C4") (pin "2") (pinfunction "2_2") (pintype "passive"))
      (node (ref "C5") (pin "2") (pinfunction "2_2") (pintype "passive"))
      (node (ref "COUT_EXT") (pin "-") (pinfunction "-_-") (pintype "passive"))
      (node (ref "DCM290P138T600A40") (pin "OUT-_1") (pinfunction "OUT-_1_OUT-_1") (pintype "bidirectional"))
      (node (ref "DCM290P138T600A40") (pin "OUT-_2") (pinfunction "OUT-_2_OUT-_2") (pintype "bidirectional"))
      (node (ref "IC1") (pin "1") (pinfunction "GND_1") (pintype "power_in"))
      (node (ref "R12") (pin "1") (pinfunction "1_1") (pintype "passive"))
      (node (ref "R13") (pin "1") (pinfunction "1_1") (pintype "passive"))
      (node (ref "R17") (pin "1") (pinfunction "1_1") (pintype "passive"))
      (node (ref "R19") (pin "1") (pinfunction "1_1") (pintype "passive"))
      (node (ref "R2") (pin "1") (pinfunction "1_1") (pintype "passive"))
      (node (ref "R4") (pin "1") (pinfunction "1_1") (pintype "passive"))
      (node (ref "R6") (pin "1") (pinfunction "1_1") (pintype "passive"))
      (node (ref "R8") (pin "1") (pinfunction "1_1") (pintype "passive"))
      (node (ref "U$1") (pin "0") (pinfunction "0_0") (pintype "bidirectional"))
      (node (ref "U$10") (pin "3") (pinfunction "S_3") (pintype "passive"))
      (node (ref "U$11") (pin "3") (pinfunction "S_3") (pintype "passive"))
      (node (ref "U$12") (pin "3") (pinfunction "S_3") (pintype "passive"))
      (node (ref "U$14") (pin "3") (pinfunction "S_3") (pintype "passive"))
      (node (ref "U$15") (pin "GND") (pinfunction "GND_GND") (pintype "bidirectional"))
      (node (ref "U$18") (pin "2") (pinfunction "GND_2") (pintype "bidirectional"))
      (node (ref "U$23") (pin "P$9") (pinfunction "P$9_P$9") (pintype "bidirectional"))
      (node (ref "U$26") (pin "10B") (pinfunction "P$22_10B") (pintype "bidirectional"))
      (node (ref "U$27") (pin "COIL+") (pinfunction "COIL+_COIL+") (pintype "bidirectional"))
      (node (ref "U$28") (pin "COIL-") (pinfunction "COIL-_COIL-") (pintype "bidirectional"))
      (node (ref "U$29") (pin "COIL+") (pinfunction "COIL+_COIL+") (pintype "bidirectional"))
      (node (ref "U$30") (pin "COIL+") (pinfunction "COIL+_COIL+") (pintype "bidirectional"))
      (node (ref "U$34") (pin "0") (pinfunction "0_0") (pintype "bidirectional"))
      (node (ref "U$5") (pin "P$2") (pinfunction "P$2_P$2") (pintype "bidirectional"))
      (node (ref "U$5") (pin "P$4") (pinfunction "P$4_P$4") (pintype "bidirectional"))
      (node (ref "U$5") (pin "P$6") (pinfunction "P$6_P$6") (pintype "bidirectional"))
      (node (ref "U$6") (pin "P$2") (pinfunction "P$2_P$2") (pintype "bidirectional"))
      (node (ref "U$6") (pin "P$4") (pinfunction "P$4_P$4") (pintype "bidirectional"))
      (node (ref "U$6") (pin "P$6") (pinfunction "P$6_P$6") (pintype "bidirectional"))
      (node (ref "U$7") (pin "P$2") (pinfunction "P$2_P$2") (pintype "bidirectional"))
      (node (ref "U$8") (pin "2") (pinfunction "S_2") (pintype "passive"))
      (node (ref "U$9") (pin "P$1") (pinfunction "P$1_P$1") (pintype "bidirectional"))
      (node (ref "U$9") (pin "P$2") (pinfunction "P$2_P$2") (pintype "bidirectional"))
      (node (ref "U$9") (pin "P$3") (pinfunction "P$3_P$3") (pintype "bidirectional"))
      (node (ref "U$9") (pin "P$4") (pinfunction "P$4_P$4") (pintype "bidirectional"))
    )
    (net (code "10") (name "HV+_DRY_FUSED") (class "Default")
      (node (ref "D2") (pin "C") (pinfunction "C_C") (pintype "passive"))
      (node (ref "HV+_FUSE_DRY") (pin "P$1") (pinfunction "P$1_P$1") (pintype "bidirectional"))
    )
    (net (code "11") (name "HV+_WET") (class "Default")
      (node (ref "U$31") (pin "A1") (pinfunction "A1_A1") (pintype "bidirectional"))
      (node (ref "U$35") (pin "2") (pinfunction "P$2_2") (pintype "bidirectional"))
    )
    (net (code "12") (name "HV-_DRY") (class "Default")
      (node (ref "OK3") (pin "2") (pinfunction "C_2") (pintype "passive"))
    )
    (net (code "13") (name "HV-_WET") (class "Default")
      (node (ref "U$32") (pin "A2") (pinfunction "A2_A2") (pintype "bidirectional"))
    )
    (net (code "14") (name "IMD+") (class "Default")
      (node (ref "IMD") (pin "R1") (pinfunction "2A_R1") (pintype "passive"))
      (node (ref "IMD") (pin "R2") (pinfunction "2B_R2") (pintype "passive"))
      (node (ref "U$5") (pin "P$1") (pinfunction "P$1_P$1") (pintype "bidirectional"))
    )
    (net (code "15") (name "MON+") (class "Default")
      (node (ref "MONITOR") (pin "R1") (pinfunction "2A_R1") (pintype "passive"))
      (node (ref "MONITOR") (pin "R2") (pinfunction "2B_R2") (pintype "passive"))
      (node (ref "U$5") (pin "P$5") (pinfunction "P$5_P$5") (pintype "bidirectional"))
    )
    (net (code "16") (name "NO1A") (class "Default")
      (node (ref "U$25") (pin "P$9") (pinfunction "P$9_P$9") (pintype "bidirectional"))
      (node (ref "U$26") (pin "9A") (pinfunction "P$9_9A") (pintype "bidirectional"))
      (node (ref "U$29") (pin "NOA3") (pinfunction "NOA3_NOA3") (pintype "bidirectional"))
    )
    (net (code "17") (name "NO1B") (class "Default")
      (node (ref "U$25") (pin "P$10") (pinfunction "P$10_P$10") (pintype "bidirectional"))
      (node (ref "U$26") (pin "10A") (pinfunction "P$10_10A") (pintype "bidirectional"))
      (node (ref "U$29") (pin "NOB3") (pinfunction "NOB3_NOB3") (pintype "bidirectional"))
    )
    (net (code "18") (name "NO2A") (class "Default")
      (node (ref "U$25") (pin "P$11") (pinfunction "P$11_P$11") (pintype "bidirectional"))
      (node (ref "U$26") (pin "11A") (pinfunction "P$11_11A") (pintype "bidirectional"))
      (node (ref "U$29") (pin "NOA2") (pinfunction "NOA2_NOA2") (pintype "bidirectional"))
    )
    (net (code "19") (name "NO2B") (class "Default")
      (node (ref "U$25") (pin "P$12") (pinfunction "P$12_P$12") (pintype "bidirectional"))
      (node (ref "U$26") (pin "12A") (pinfunction "P$12_12A") (pintype "bidirectional"))
      (node (ref "U$29") (pin "NOB2") (pinfunction "NOB2_NOB2") (pintype "bidirectional"))
    )
    (net (code "20") (name "NO3A") (class "Default")
      (node (ref "U$23") (pin "P$1") (pinfunction "P$1_P$1") (pintype "bidirectional"))
      (node (ref "U$26") (pin "1B") (pinfunction "P$13_1B") (pintype "bidirectional"))
      (node (ref "U$29") (pin "NOA1") (pinfunction "NOA1_NOA1") (pintype "bidirectional"))
    )
    (net (code "21") (name "NO3B") (class "Default")
      (node (ref "U$23") (pin "P$2") (pinfunction "P$2_P$2") (pintype "bidirectional"))
      (node (ref "U$26") (pin "2B") (pinfunction "P$14_2B") (pintype "bidirectional"))
      (node (ref "U$29") (pin "NOB1") (pinfunction "NOB1_NOB1") (pintype "bidirectional"))
    )
    (net (code "22") (name "NO4A") (class "Default")
      (node (ref "U$23") (pin "P$3") (pinfunction "P$3_P$3") (pintype "bidirectional"))
      (node (ref "U$26") (pin "3B") (pinfunction "P$15_3B") (pintype "bidirectional"))
      (node (ref "U$30") (pin "NOA3") (pinfunction "NOA3_NOA3") (pintype "bidirectional"))
    )
    (net (code "23") (name "NO4B") (class "Default")
      (node (ref "U$23") (pin "P$4") (pinfunction "P$4_P$4") (pintype "bidirectional"))
      (node (ref "U$26") (pin "4B") (pinfunction "P$16_4B") (pintype "bidirectional"))
      (node (ref "U$30") (pin "NOB3") (pinfunction "NOB3_NOB3") (pintype "bidirectional"))
    )
    (net (code "24") (name "NO5A") (class "Default")
      (node (ref "U$23") (pin "P$5") (pinfunction "P$5_P$5") (pintype "bidirectional"))
      (node (ref "U$26") (pin "5B") (pinfunction "P$17_5B") (pintype "bidirectional"))
      (node (ref "U$30") (pin "NOA2") (pinfunction "NOA2_NOA2") (pintype "bidirectional"))
    )
    (net (code "25") (name "NO5B") (class "Default")
      (node (ref "U$23") (pin "P$6") (pinfunction "P$6_P$6") (pintype "bidirectional"))
      (node (ref "U$26") (pin "6B") (pinfunction "P$18_6B") (pintype "bidirectional"))
      (node (ref "U$30") (pin "NOB2") (pinfunction "NOB2_NOB2") (pintype "bidirectional"))
    )
    (net (code "26") (name "NO6A") (class "Default")
      (node (ref "U$23") (pin "P$7") (pinfunction "P$7_P$7") (pintype "bidirectional"))
      (node (ref "U$26") (pin "7B") (pinfunction "P$19_7B") (pintype "bidirectional"))
      (node (ref "U$30") (pin "NOA1") (pinfunction "NOA1_NOA1") (pintype "bidirectional"))
    )
    (net (code "27") (name "NO6B") (class "Default")
      (node (ref "U$23") (pin "P$8") (pinfunction "P$8_P$8") (pintype "bidirectional"))
      (node (ref "U$26") (pin "8B") (pinfunction "P$20_8B") (pintype "bidirectional"))
      (node (ref "U$30") (pin "NOB1") (pinfunction "NOB1_NOB1") (pintype "bidirectional"))
    )
    (net (code "28") (name "Net-(1A_500V_FUSE_ENERGYMETER-PadP$2)") (class "Default")
      (node (ref "1A_500V_FUSE_ENERGYMETER") (pin "P$2") (pinfunction "P$2_P$2") (pintype "bidirectional"))
      (node (ref "U$17") (pin "P$1") (pinfunction "P$1_P$1") (pintype "bidirectional"))
    )
    (net (code "29") (name "Net-(1A_500V_FUSE_IMD_VSENSE-PadP$2)") (class "Default")
      (node (ref "1A_500V_FUSE_IMD_VSENSE") (pin "P$2") (pinfunction "P$2_P$2") (pintype "bidirectional"))
      (node (ref "U$17") (pin "P$2") (pinfunction "P$2_P$2") (pintype "bidirectional"))
    )
    (net (code "30") (name "Net-(CFILTER_1-1)") (class "Default")
      (node (ref "CFILTER_1") (pin "P$1") (pinfunction "1_P$1") (pintype "passive"))
      (node (ref "CFILTER_2") (pin "P$1") (pinfunction "1_P$1") (pintype "passive"))
      (node (ref "DCM290P138T600A40") (pin "IN+") (pinfunction "IN+_IN+") (pintype "bidirectional"))
      (node (ref "L_IN") (pin "P$2") (pinfunction "2_P$2") (pintype "passive"))
      (node (ref "R_IN") (pin "2") (pinfunction "2_2") (pintype "passive"))
    )
    (net (code "31") (name "Net-(IC1-CON)") (class "Default")
      (node (ref "C2") (pin "1") (pinfunction "1_1") (pintype "passive"))
      (node (ref "IC1") (pin "5") (pinfunction "CON_5") (pintype "input"))
    )
    (net (code "32") (name "Net-(IC1-DIS)") (class "Default")
      (node (ref "IC1") (pin "7") (pinfunction "DIS_7") (pintype "input"))
      (node (ref "R10") (pin "2") (pinfunction "2_2") (pintype "passive"))
      (node (ref "R9") (pin "1") (pinfunction "1_1") (pintype "passive"))
    )
    (net (code "33") (name "Net-(IC1-OUT)") (class "Default")
      (node (ref "IC1") (pin "3") (pinfunction "OUT_3") (pintype "output"))
      (node (ref "R7") (pin "1") (pinfunction "1_1") (pintype "passive"))
      (node (ref "R8") (pin "2") (pinfunction "2_2") (pintype "passive"))
    )
    (net (code "34") (name "Net-(IC1-TRE)") (class "Default")
      (node (ref "C1") (pin "1") (pinfunction "1_1") (pintype "passive"))
      (node (ref "IC1") (pin "2") (pinfunction "TRI_2") (pintype "input"))
      (node (ref "IC1") (pin "6") (pinfunction "TRE_6") (pintype "input"))
      (node (ref "R10") (pin "1") (pinfunction "1_1") (pintype "passive"))
    )
    (net (code "35") (name "Net-(L_IN-1)") (class "Default")
      (node (ref "INPUT_FUSE") (pin "P$2") (pinfunction "P$2_P$2") (pintype "bidirectional"))
      (node (ref "L_IN") (pin "P$1") (pinfunction "1_P$1") (pintype "passive"))
      (node (ref "R_IN") (pin "1") (pinfunction "1_1") (pintype "passive"))
    )
    (net (code "36") (name "Net-(OK3-A)") (class "Default")
      (node (ref "OK3") (pin "1") (pinfunction "A_1") (pintype "passive"))
      (node (ref "R16") (pin "1") (pinfunction "1_1") (pintype "passive"))
    )
    (net (code "37") (name "Net-(OK3-EMIT)") (class "Default")
      (node (ref "D4") (pin "A") (pinfunction "A_A") (pintype "passive"))
      (node (ref "OK3") (pin "3") (pinfunction "EMIT_3") (pintype "passive"))
      (node (ref "R17") (pin "2") (pinfunction "2_2") (pintype "passive"))
    )
    (net (code "38") (name "Net-(R1-Pad1)") (class "Default")
      (node (ref "R1") (pin "1") (pinfunction "1_1") (pintype "passive"))
      (node (ref "R2") (pin "2") (pinfunction "2_2") (pintype "passive"))
    )
    (net (code "39") (name "Net-(U$1-Pad1)") (class "Default")
      (node (ref "U$1") (pin "1") (pinfunction "1_1") (pintype "bidirectional"))
      (node (ref "U$32") (pin "T1") (pinfunction "T1_T1") (pintype "bidirectional"))
    )
    (net (code "40") (name "Net-(U$1-Pad4)") (class "Default")
      (node (ref "U$1") (pin "4") (pinfunction "4_4") (pintype "bidirectional"))
      (node (ref "U$1") (pin "6") (pinfunction "6_6") (pintype "bidirectional"))
    )
    (net (code "41") (name "Net-(U$4-P$1)") (class "Default")
      (node (ref "U$1") (pin "8") (pinfunction "8_8") (pintype "bidirectional"))
      (node (ref "U$4") (pin "1") (pinfunction "P$1_1") (pintype "bidirectional"))
    )
    (net (code "42") (name "Net-(U$8-D)") (class "Default")
      (node (ref "R14") (pin "2") (pinfunction "2_2") (pintype "passive"))
      (node (ref "U$8") (pin "3") (pinfunction "D_3") (pintype "passive"))
    )
    (net (code "43") (name "Net-(U$11-G)") (class "Default")
      (node (ref "R1") (pin "2") (pinfunction "2_2") (pintype "passive"))
      (node (ref "U$11") (pin "1") (pinfunction "G_1") (pintype "passive"))
      (node (ref "U$15") (pin "GATE") (pinfunction "GATE_GATE") (pintype "bidirectional"))
    )
    (net (code "44") (name "Net-(U$12-D)") (class "Default")
      (node (ref "D1") (pin "A") (pinfunction "A_A") (pintype "passive"))
      (node (ref "R11") (pin "1") (pinfunction "1_1") (pintype "passive"))
      (node (ref "U$12") (pin "2") (pinfunction "D_2") (pintype "passive"))
    )
    (net (code "45") (name "Net-(U$12-G)") (class "Default")
      (node (ref "R3") (pin "2") (pinfunction "2_2") (pintype "passive"))
      (node (ref "U$12") (pin "1") (pinfunction "G_1") (pintype "passive"))
    )
    (net (code "46") (name "Net-(U$13-G)") (class "Default")
      (node (ref "R5") (pin "2") (pinfunction "2_2") (pintype "passive"))
      (node (ref "U$13") (pin "1") (pinfunction "G_1") (pintype "passive"))
    )
    (net (code "47") (name "Net-(U$13-S)") (class "Default")
      (node (ref "U$13") (pin "3") (pinfunction "S_3") (pintype "passive"))
      (node (ref "U$14") (pin "2") (pinfunction "D_2") (pintype "passive"))
    )
    (net (code "48") (name "Net-(U$14-G)") (class "Default")
      (node (ref "R7") (pin "2") (pinfunction "2_2") (pintype "passive"))
      (node (ref "U$14") (pin "1") (pinfunction "G_1") (pintype "passive"))
    )
    (net (code "49") (name "Net-(U$18-OUT)") (class "Default")
      (node (ref "R12") (pin "2") (pinfunction "2_2") (pintype "passive"))
      (node (ref "U$18") (pin "5") (pinfunction "OUT_5") (pintype "bidirectional"))
      (node (ref "U$8") (pin "1") (pinfunction "G_1") (pintype "passive"))
    )
    (net (code "50") (name "Net-(U$19-A)") (class "Default")
      (node (ref "D2") (pin "A") (pinfunction "A_A") (pintype "passive"))
      (node (ref "U$19") (pin "3") (pinfunction "A_3") (pintype "bidirectional"))
    )
    (net (code "51") (name "Net-(U$19-K)") (class "Default")
      (node (ref "R16") (pin "2") (pinfunction "2_2") (pintype "passive"))
      (node (ref "U$19") (pin "2") (pinfunction "K_2") (pintype "bidirectional"))
    )
    (net (code "52") (name "Net-(U$20-G)") (class "Default")
      (node (ref "R14") (pin "1") (pinfunction "1_1") (pintype "passive"))
      (node (ref "R15") (pin "2") (pinfunction "2_2") (pintype "passive"))
      (node (ref "U$20") (pin "4") (pinfunction "G_4") (pintype "passive"))
      (node (ref "U$21") (pin "4") (pinfunction "G_4") (pintype "passive"))
      (node (ref "U$22") (pin "4") (pinfunction "G_4") (pintype "passive"))
    )
    (net (code "53") (name "Net-(U$27-PadNOB3)") (class "Default")
      (node (ref "U$27") (pin "NOB3") (pinfunction "NOB3_NOB3") (pintype "bidirectional"))
      (node (ref "U$28") (pin "NOA3") (pinfunction "NOA3_NOA3") (pintype "bidirectional"))
    )
    (net (code "54") (name "Net-(U$28-PadNOB3)") (class "Default")
      (node (ref "U$28") (pin "NOB3") (pinfunction "NOB3_NOB3") (pintype "bidirectional"))
      (node (ref "U$29") (pin "COIL-") (pinfunction "COIL-_COIL-") (pintype "bidirectional"))
      (node (ref "U$30") (pin "COIL-") (pinfunction "COIL-_COIL-") (pintype "bidirectional"))
    )
    (net (code "55") (name "Net-(U$31-PadX2)") (class "Default")
      (node (ref "U$31") (pin "X2") (pinfunction "X2_X2") (pintype "bidirectional"))
      (node (ref "U$32") (pin "X1") (pinfunction "X1_X1") (pintype "bidirectional"))
    )
    (net (code "56") (name "Net-(U$34-Pad4)") (class "Default")
      (node (ref "U$34") (pin "4") (pinfunction "4_4") (pintype "bidirectional"))
      (node (ref "U$34") (pin "6") (pinfunction "6_6") (pintype "bidirectional"))
    )
    (net (code "57") (name "Net-(U$35-P$1)") (class "Default")
      (node (ref "U$34") (pin "8") (pinfunction "8_8") (pintype "bidirectional"))
      (node (ref "U$35") (pin "1") (pinfunction "P$1_1") (pintype "bidirectional"))
    )
    (net (code "58") (name "PRECH_ACTIVE") (class "Default")
      (node (ref "R13") (pin "2") (pinfunction "2_2") (pintype "passive"))
      (node (ref "U$18") (pin "4") (pinfunction "IN-_4") (pintype "bidirectional"))
      (node (ref "X1") (pin "1") (pinfunction "K_1") (pintype "passive"))
      (node (ref "X1") (pin "2") (pinfunction "K_2") (pintype "passive"))
    )
    (net (code "59") (name "RST1IN") (class "Default")
      (node (ref "U$25") (pin "P$6") (pinfunction "P$6_P$6") (pintype "bidirectional"))
      (node (ref "U$26") (pin "6A") (pinfunction "P$6_6A") (pintype "bidirectional"))
      (node (ref "U$27") (pin "NOB2") (pinfunction "NOB2_NOB2") (pintype "bidirectional"))
      (node (ref "U$28") (pin "COIL+") (pinfunction "COIL+_COIL+") (pintype "bidirectional"))
    )
    (net (code "60") (name "RST2IN") (class "Default")
      (node (ref "U$25") (pin "P$8") (pinfunction "P$8_P$8") (pintype "bidirectional"))
      (node (ref "U$26") (pin "8A") (pinfunction "P$8_8A") (pintype "bidirectional"))
      (node (ref "U$27") (pin "COIL-") (pinfunction "COIL-_COIL-") (pintype "bidirectional"))
      (node (ref "U$28") (pin "NOA2") (pinfunction "NOA2_NOA2") (pintype "bidirectional"))
    )
    (net (code "61") (name "SAFETY+") (class "Default")
      (node (ref "U$31") (pin "X1") (pinfunction "X1_X1") (pintype "bidirectional"))
    )
    (net (code "62") (name "SAFETY-") (class "Default")
      (node (ref "U$32") (pin "X2") (pinfunction "X2_X2") (pintype "bidirectional"))
    )
    (net (code "63") (name "SPR1PWR") (class "Default")
      (node (ref "SPR1") (pin "R1") (pinfunction "2A_R1") (pintype "passive"))
      (node (ref "SPR1") (pin "R2") (pinfunction "2B_R2") (pintype "passive"))
      (node (ref "U$6") (pin "P$3") (pinfunction "P$3_P$3") (pintype "bidirectional"))
    )
    (net (code "64") (name "SPR2PWR") (class "Default")
      (node (ref "SPR2") (pin "R1") (pinfunction "2A_R1") (pintype "passive"))
      (node (ref "SPR2") (pin "R2") (pinfunction "2B_R2") (pintype "passive"))
      (node (ref "U$6") (pin "P$5") (pinfunction "P$5_P$5") (pintype "bidirectional"))
    )
    (net (code "65") (name "TSAL_GRN_GND") (class "Default")
      (node (ref "R3") (pin "1") (pinfunction "1_1") (pintype "passive"))
      (node (ref "R4") (pin "2") (pinfunction "2_2") (pintype "passive"))
      (node (ref "U$11") (pin "2") (pinfunction "D_2") (pintype "passive"))
      (node (ref "U$7") (pin "P$5") (pinfunction "P$5_P$5") (pintype "bidirectional"))
    )
    (net (code "66") (name "TSAL_RED_GND") (class "Default")
      (node (ref "U$13") (pin "2") (pinfunction "D_2") (pintype "passive"))
      (node (ref "U$7") (pin "P$4") (pinfunction "P$4_P$4") (pintype "bidirectional"))
    )
    (net (code "67") (name "V+") (class "Default")
      (node (ref "HV+_FUSE_DRY") (pin "P$2") (pinfunction "P$2_P$2") (pintype "bidirectional"))
      (node (ref "INPUT_FUSE") (pin "P$1") (pinfunction "P$1_P$1") (pintype "bidirectional"))
      (node (ref "U$16") (pin "P$1") (pinfunction "P$1_P$1") (pintype "bidirectional"))
      (node (ref "U$31") (pin "A2") (pinfunction "A2_A2") (pintype "bidirectional"))
      (node (ref "U$34") (pin "2") (pinfunction "2_2") (pintype "bidirectional"))
      (node (ref "U$4") (pin "2") (pinfunction "P$2_2") (pintype "bidirectional"))
    )
    (net (code "68") (name "V-") (class "Default")
      (node (ref "1A_500V_FUSE_ENERGYMETER") (pin "P$1") (pinfunction "P$1_P$1") (pintype "bidirectional"))
      (node (ref "1A_500V_FUSE_IMD_VSENSE") (pin "P$1") (pinfunction "P$1_P$1") (pintype "bidirectional"))
      (node (ref "CFILTER_1") (pin "P$2") (pinfunction "2_P$2") (pintype "passive"))
      (node (ref "CFILTER_2") (pin "P$2") (pinfunction "2_P$2") (pintype "passive"))
      (node (ref "DCM290P138T600A40") (pin "IN-") (pinfunction "IN-_IN-") (pintype "bidirectional"))
      (node (ref "U$1") (pin "2") (pinfunction "2_2") (pintype "bidirectional"))
      (node (ref "U$16") (pin "P$2") (pinfunction "P$2_P$2") (pintype "bidirectional"))
      (node (ref "U$19") (pin "1") (pinfunction "G_1") (pintype "bidirectional"))
      (node (ref "U$32") (pin "A1") (pinfunction "A1_A1") (pintype "bidirectional"))
    )
    (net (code "69") (name "unconnected-(DCM290P138T600A40-PadEN)") (class "Default")
      (node (ref "DCM290P138T600A40") (pin "EN") (pinfunction "EN_EN") (pintype "bidirectional"))
    )
    (net (code "70") (name "unconnected-(DCM290P138T600A40-PadFT)") (class "Default")
      (node (ref "DCM290P138T600A40") (pin "FT") (pinfunction "FT_FT") (pintype "bidirectional"))
    )
    (net (code "71") (name "unconnected-(DCM290P138T600A40-PadTR)") (class "Default")
      (node (ref "DCM290P138T600A40") (pin "TR") (pinfunction "TR_TR") (pintype "bidirectional"))
    )
    (net (code "72") (name "unconnected-(U$7-PadP$8)") (class "Default")
      (node (ref "U$7") (pin "P$8") (pinfunction "P$8_P$8") (pintype "bidirectional"))
    )
    (net (code "73") (name "unconnected-(U$7-PadP$9)") (class "Default")
      (node (ref "U$7") (pin "P$9") (pinfunction "P$9_P$9") (pintype "bidirectional"))
    )
    (net (code "74") (name "unconnected-(U$23-PadP$11)") (class "Default")
      (node (ref "U$23") (pin "P$11") (pinfunction "P$11_P$11") (pintype "bidirectional"))
    )
    (net (code "75") (name "unconnected-(U$23-PadP$12)") (class "Default")
      (node (ref "U$23") (pin "P$12") (pinfunction "P$12_P$12") (pintype "bidirectional"))
    )
    (net (code "76") (name "unconnected-(U$26-P$23-Pad11B)") (class "Default")
      (node (ref "U$26") (pin "11B") (pinfunction "P$23_11B") (pintype "bidirectional"))
    )
    (net (code "77") (name "unconnected-(U$26-P$24-Pad12B)") (class "Default")
      (node (ref "U$26") (pin "12B") (pinfunction "P$24_12B") (pintype "bidirectional"))
    )
    (net (code "78") (name "unconnected-(U$27-PadNCA4)") (class "Default")
      (node (ref "U$27") (pin "NCA4") (pinfunction "NCA4_NCA4") (pintype "bidirectional"))
    )
    (net (code "79") (name "unconnected-(U$27-PadNCB4)") (class "Default")
      (node (ref "U$27") (pin "NCB4") (pinfunction "NCB4_NCB4") (pintype "bidirectional"))
    )
    (net (code "80") (name "unconnected-(U$27-PadNOA1)") (class "Default")
      (node (ref "U$27") (pin "NOA1") (pinfunction "NOA1_NOA1") (pintype "bidirectional"))
    )
    (net (code "81") (name "unconnected-(U$27-PadNOB1)") (class "Default")
      (node (ref "U$27") (pin "NOB1") (pinfunction "NOB1_NOB1") (pintype "bidirectional"))
    )
    (net (code "82") (name "unconnected-(U$28-PadNCA4)") (class "Default")
      (node (ref "U$28") (pin "NCA4") (pinfunction "NCA4_NCA4") (pintype "bidirectional"))
    )
    (net (code "83") (name "unconnected-(U$28-PadNCB4)") (class "Default")
      (node (ref "U$28") (pin "NCB4") (pinfunction "NCB4_NCB4") (pintype "bidirectional"))
    )
    (net (code "84") (name "unconnected-(U$28-PadNOA1)") (class "Default")
      (node (ref "U$28") (pin "NOA1") (pinfunction "NOA1_NOA1") (pintype "bidirectional"))
    )
    (net (code "85") (name "unconnected-(U$28-PadNOB1)") (class "Default")
      (node (ref "U$28") (pin "NOB1") (pinfunction "NOB1_NOB1") (pintype "bidirectional"))
    )
    (net (code "86") (name "unconnected-(U$29-PadNCA4)") (class "Default")
      (node (ref "U$29") (pin "NCA4") (pinfunction "NCA4_NCA4") (pintype "bidirectional"))
    )
    (net (code "87") (name "unconnected-(U$29-PadNCB4)") (class "Default")
      (node (ref "U$29") (pin "NCB4") (pinfunction "NCB4_NCB4") (pintype "bidirectional"))
    )
    (net (code "88") (name "unconnected-(U$30-PadNCA4)") (class "Default")
      (node (ref "U$30") (pin "NCA4") (pinfunction "NCA4_NCA4") (pintype "bidirectional"))
    )
    (net (code "89") (name "unconnected-(U$30-PadNCB4)") (class "Default")
      (node (ref "U$30") (pin "NCB4") (pinfunction "NCB4_NCB4") (pintype "bidirectional"))
    )
    (net (code "90") (name "unconnected-(U$31-PadT1)") (class "Default")
      (node (ref "U$31") (pin "T1") (pinfunction "T1_T1") (pintype "bidirectional"))
    )
    (net (code "91") (name "unconnected-(U$31-PadT2)") (class "Default")
      (node (ref "U$31") (pin "T2") (pinfunction "T2_T2") (pintype "bidirectional"))
    )
    (net (code "92") (name "unconnected-(U$34-Pad1)") (class "Default")
      (node (ref "U$34") (pin "1") (pinfunction "1_1") (pintype "bidirectional"))
    )
  )
)
